# transponder-11_5_2.net
KiCad netlist of a schematic drawn in EAGLE
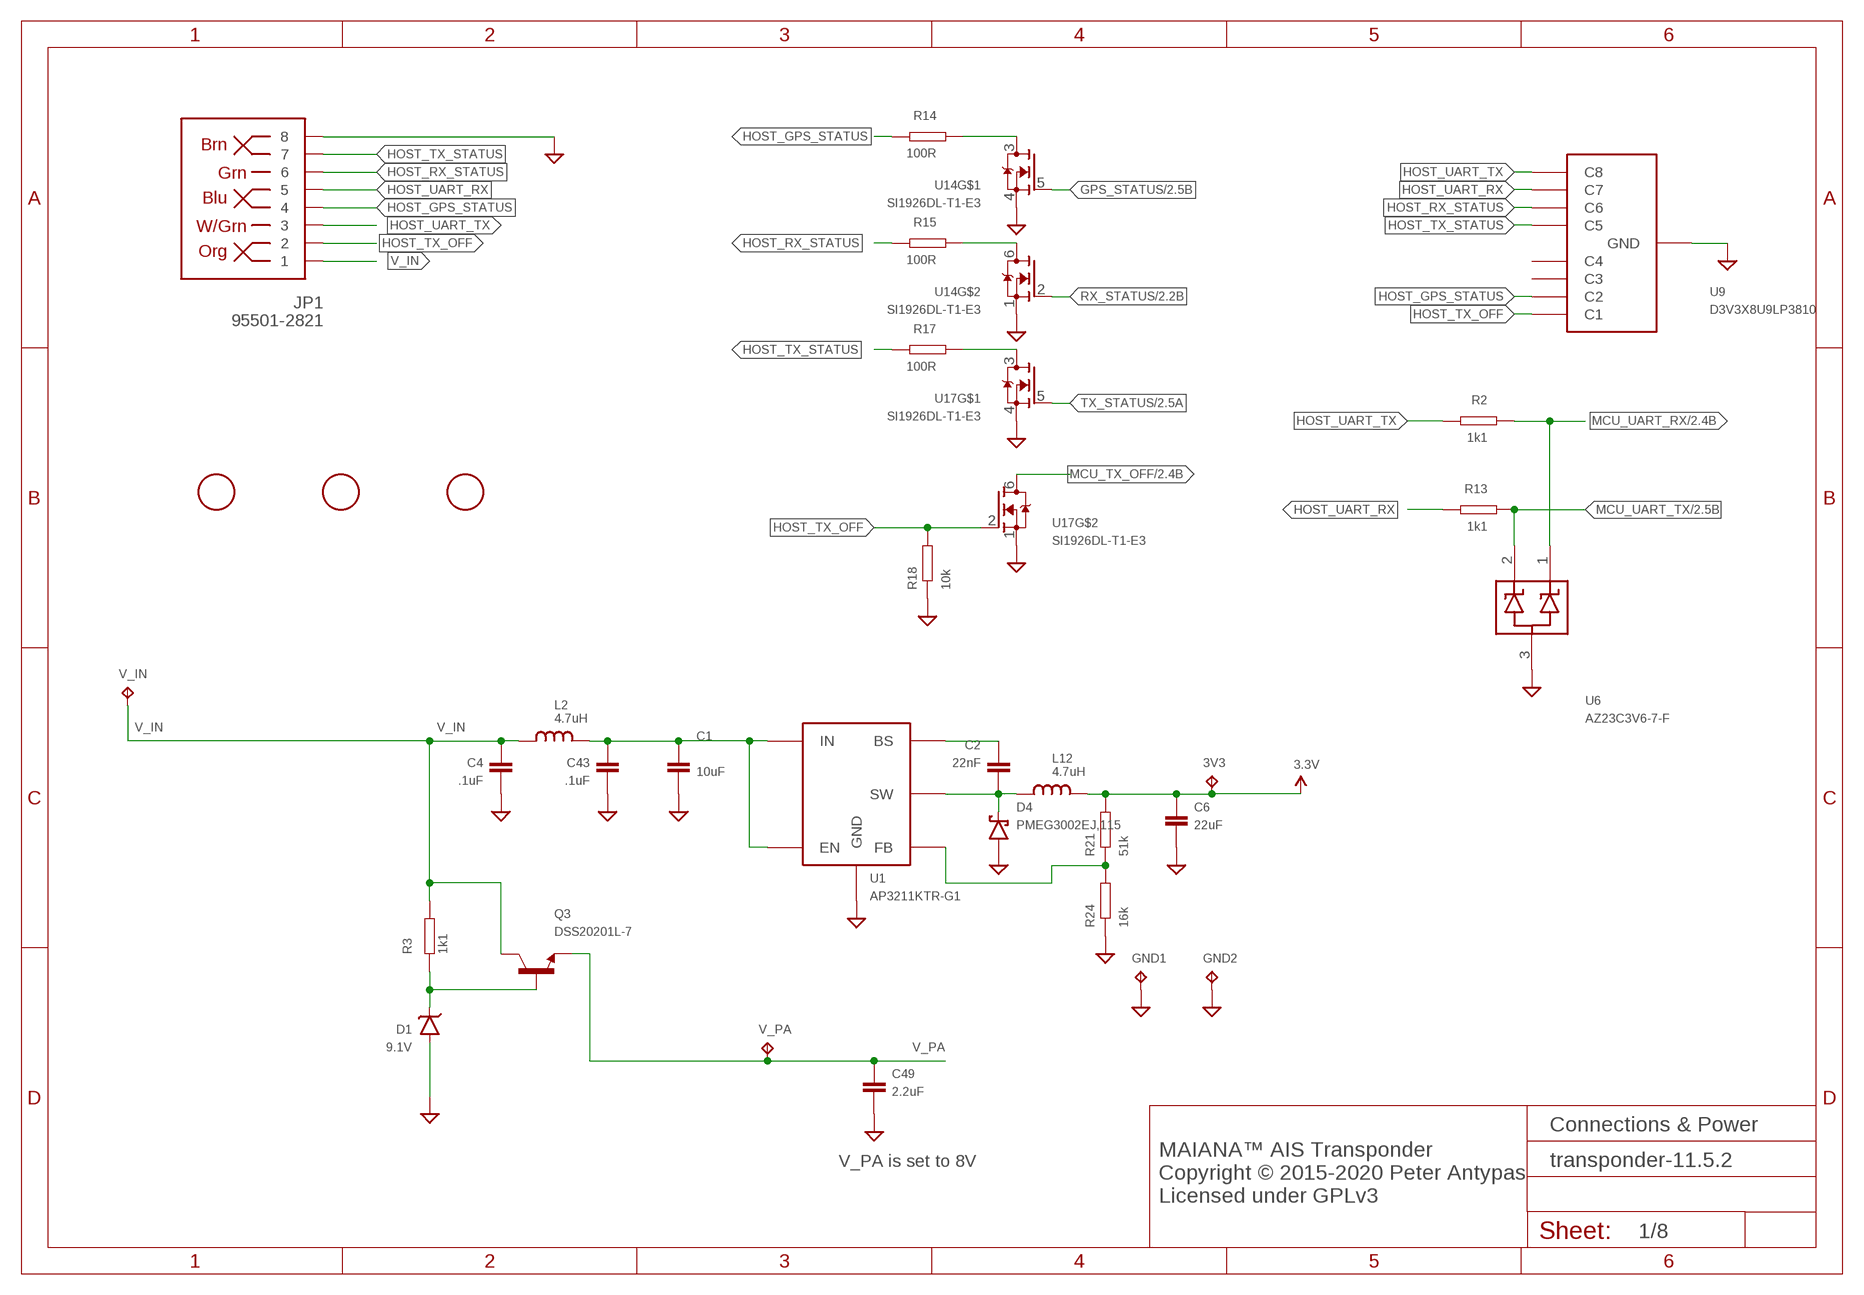
[diagram p0: schematic, sheet 1]
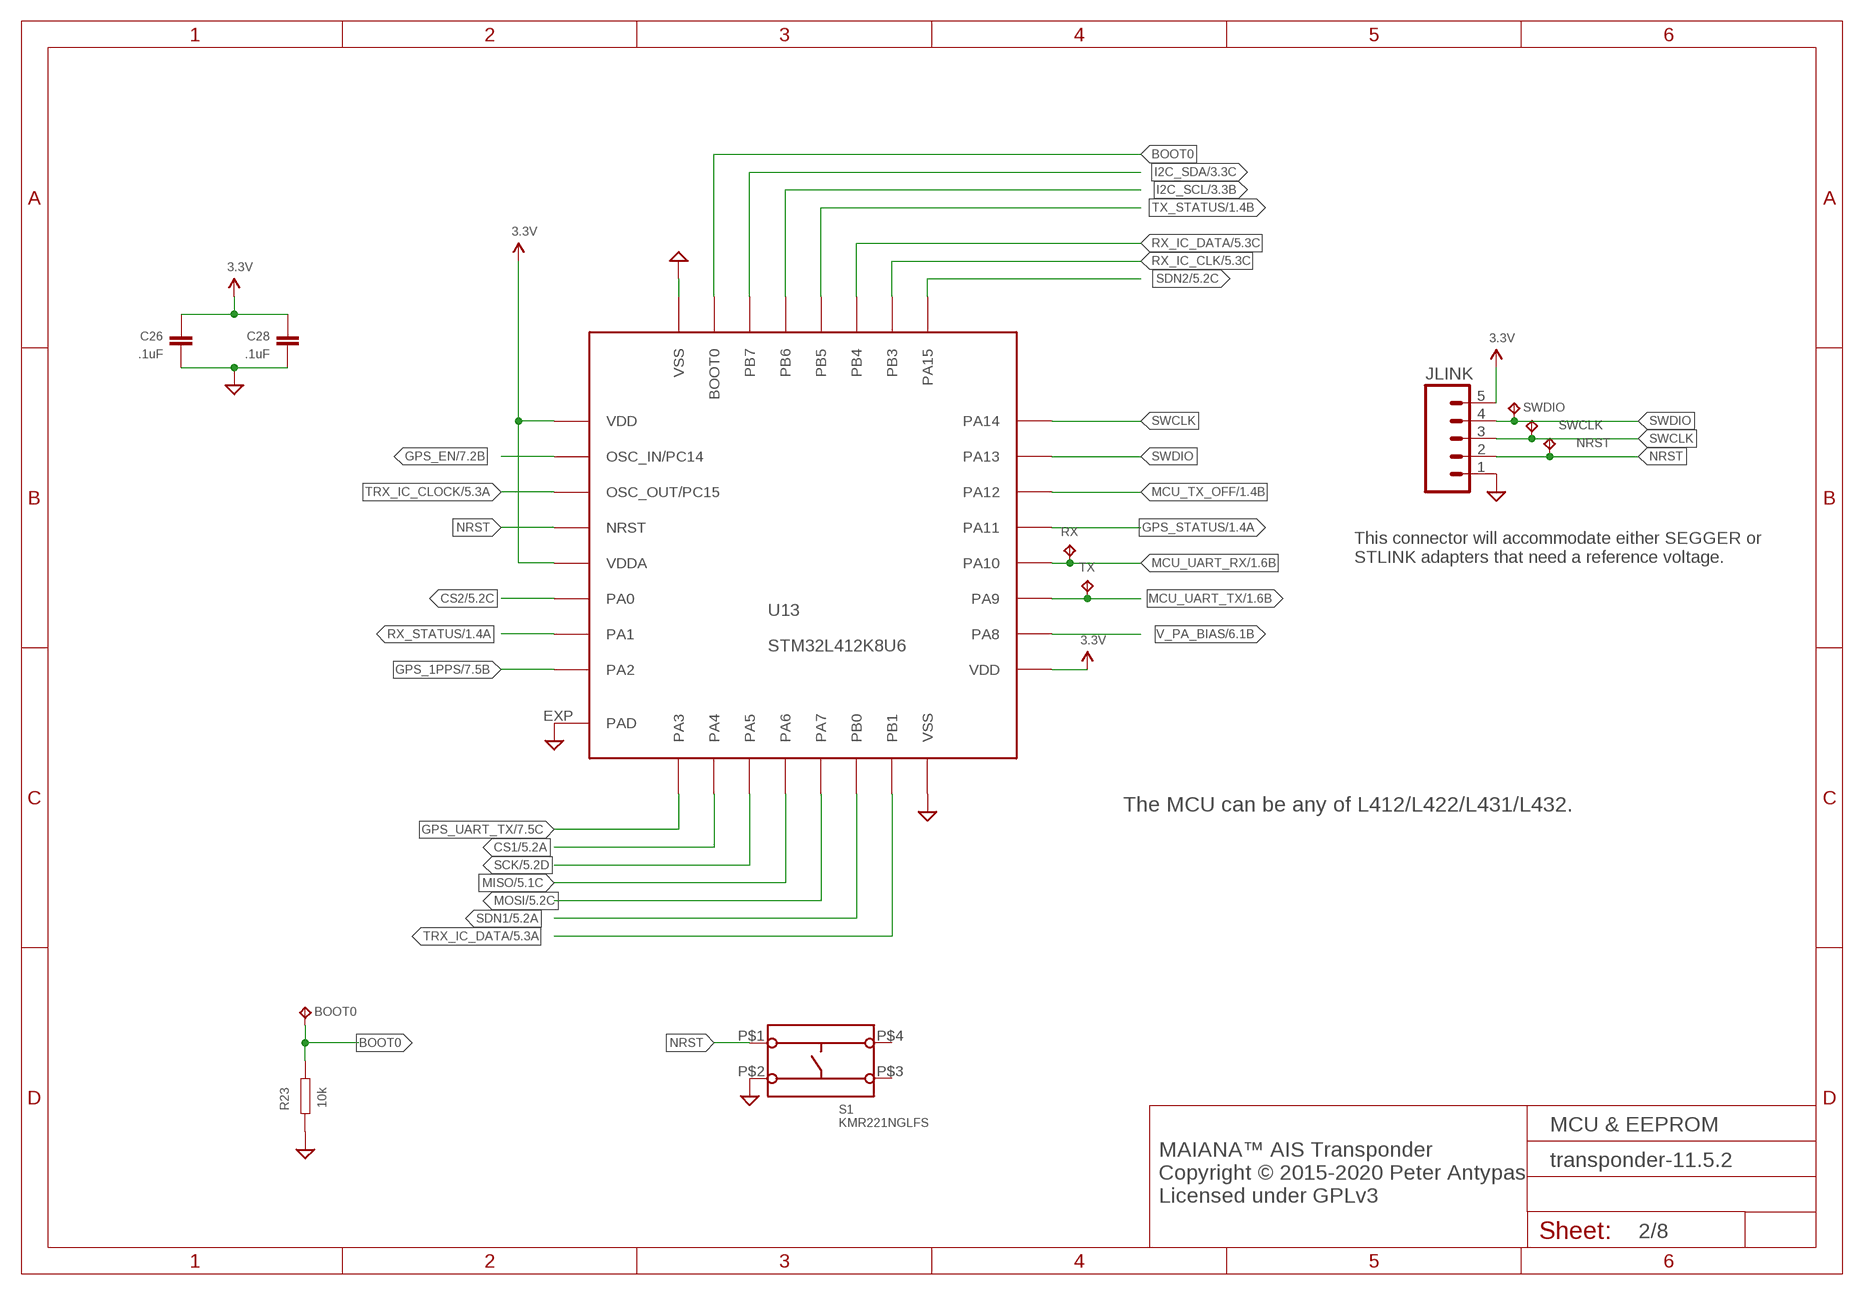
[diagram p1: schematic, sheet 2]
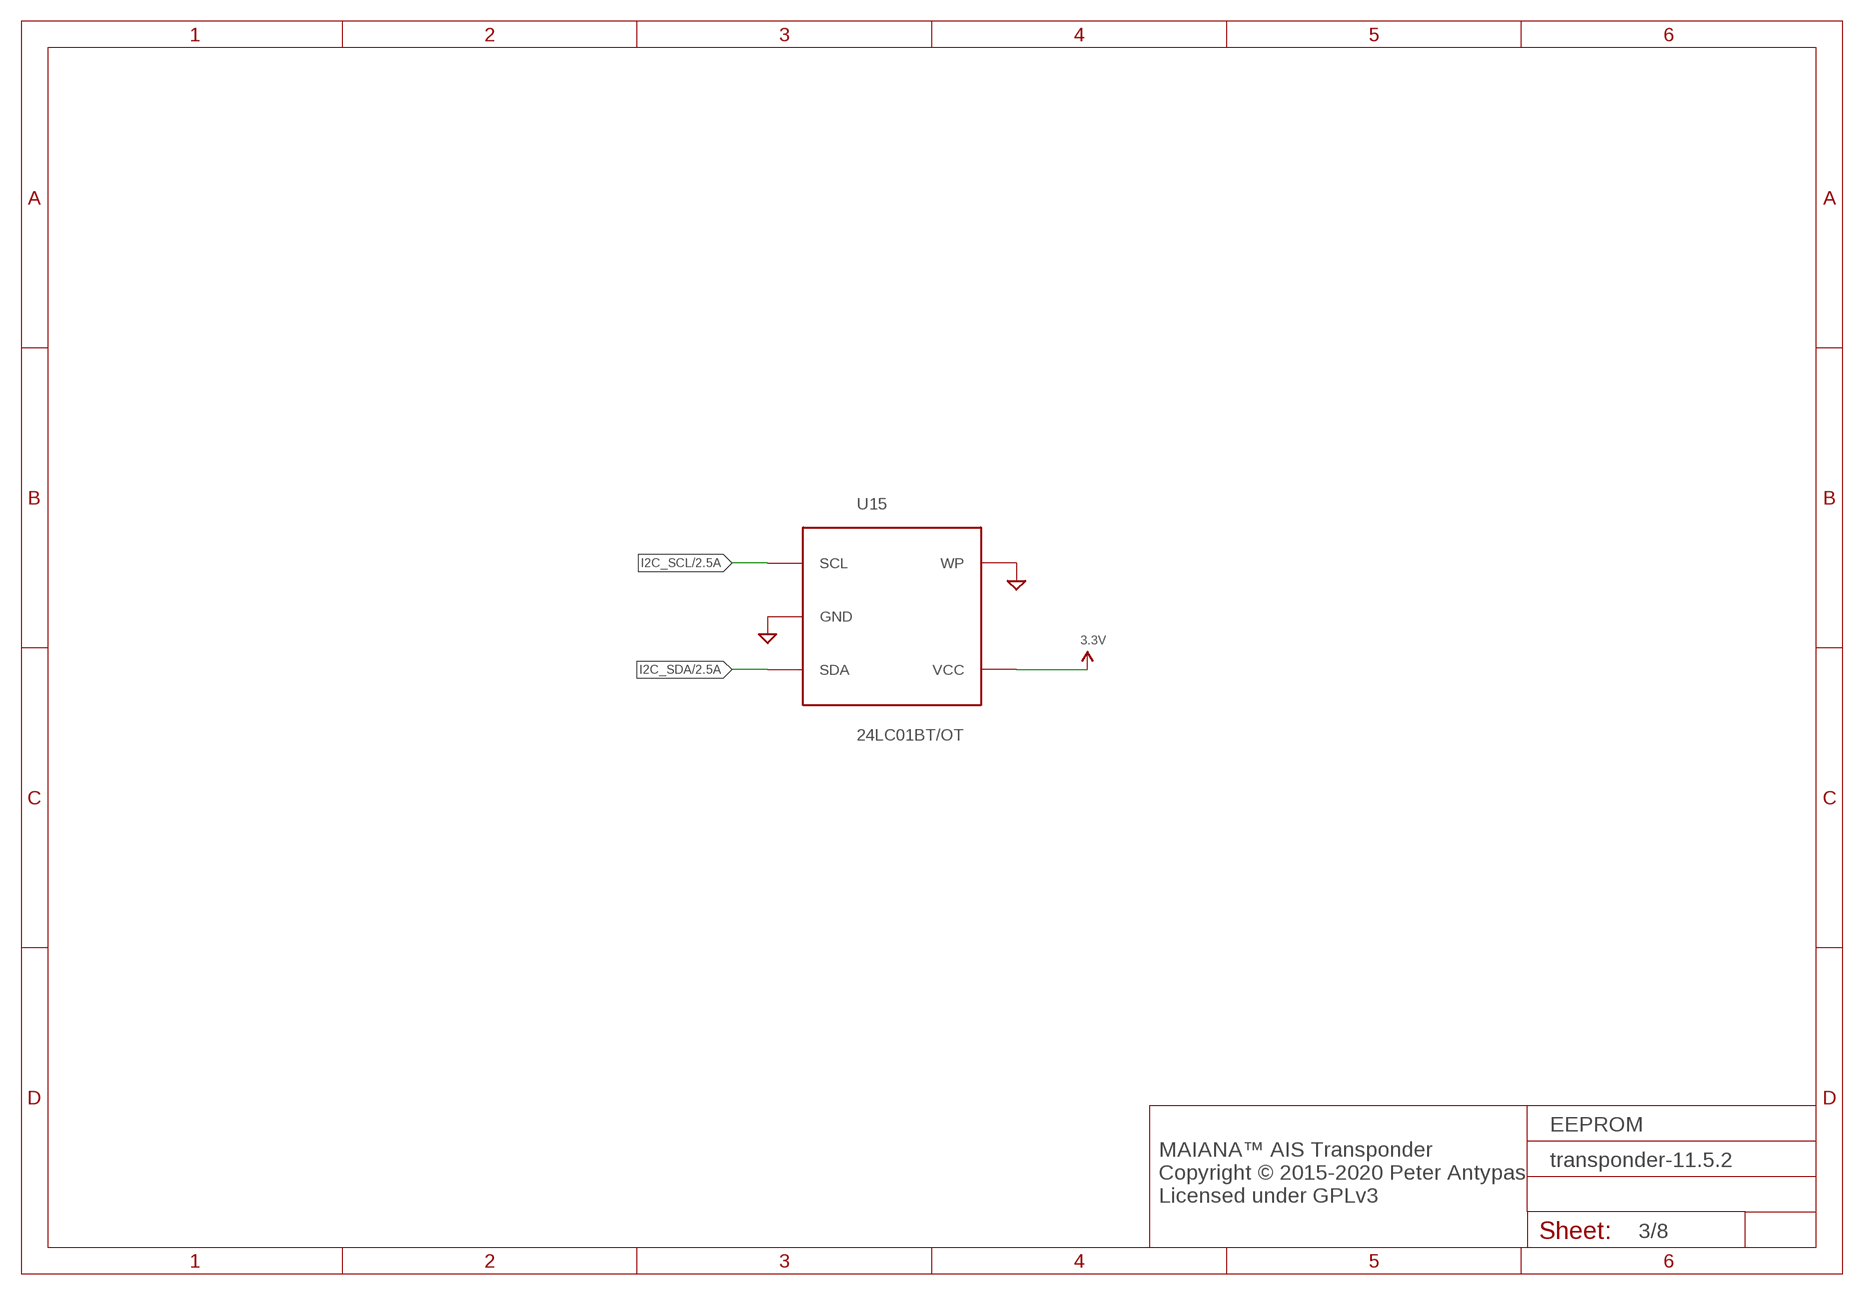
[diagram p2: schematic, sheet 3]
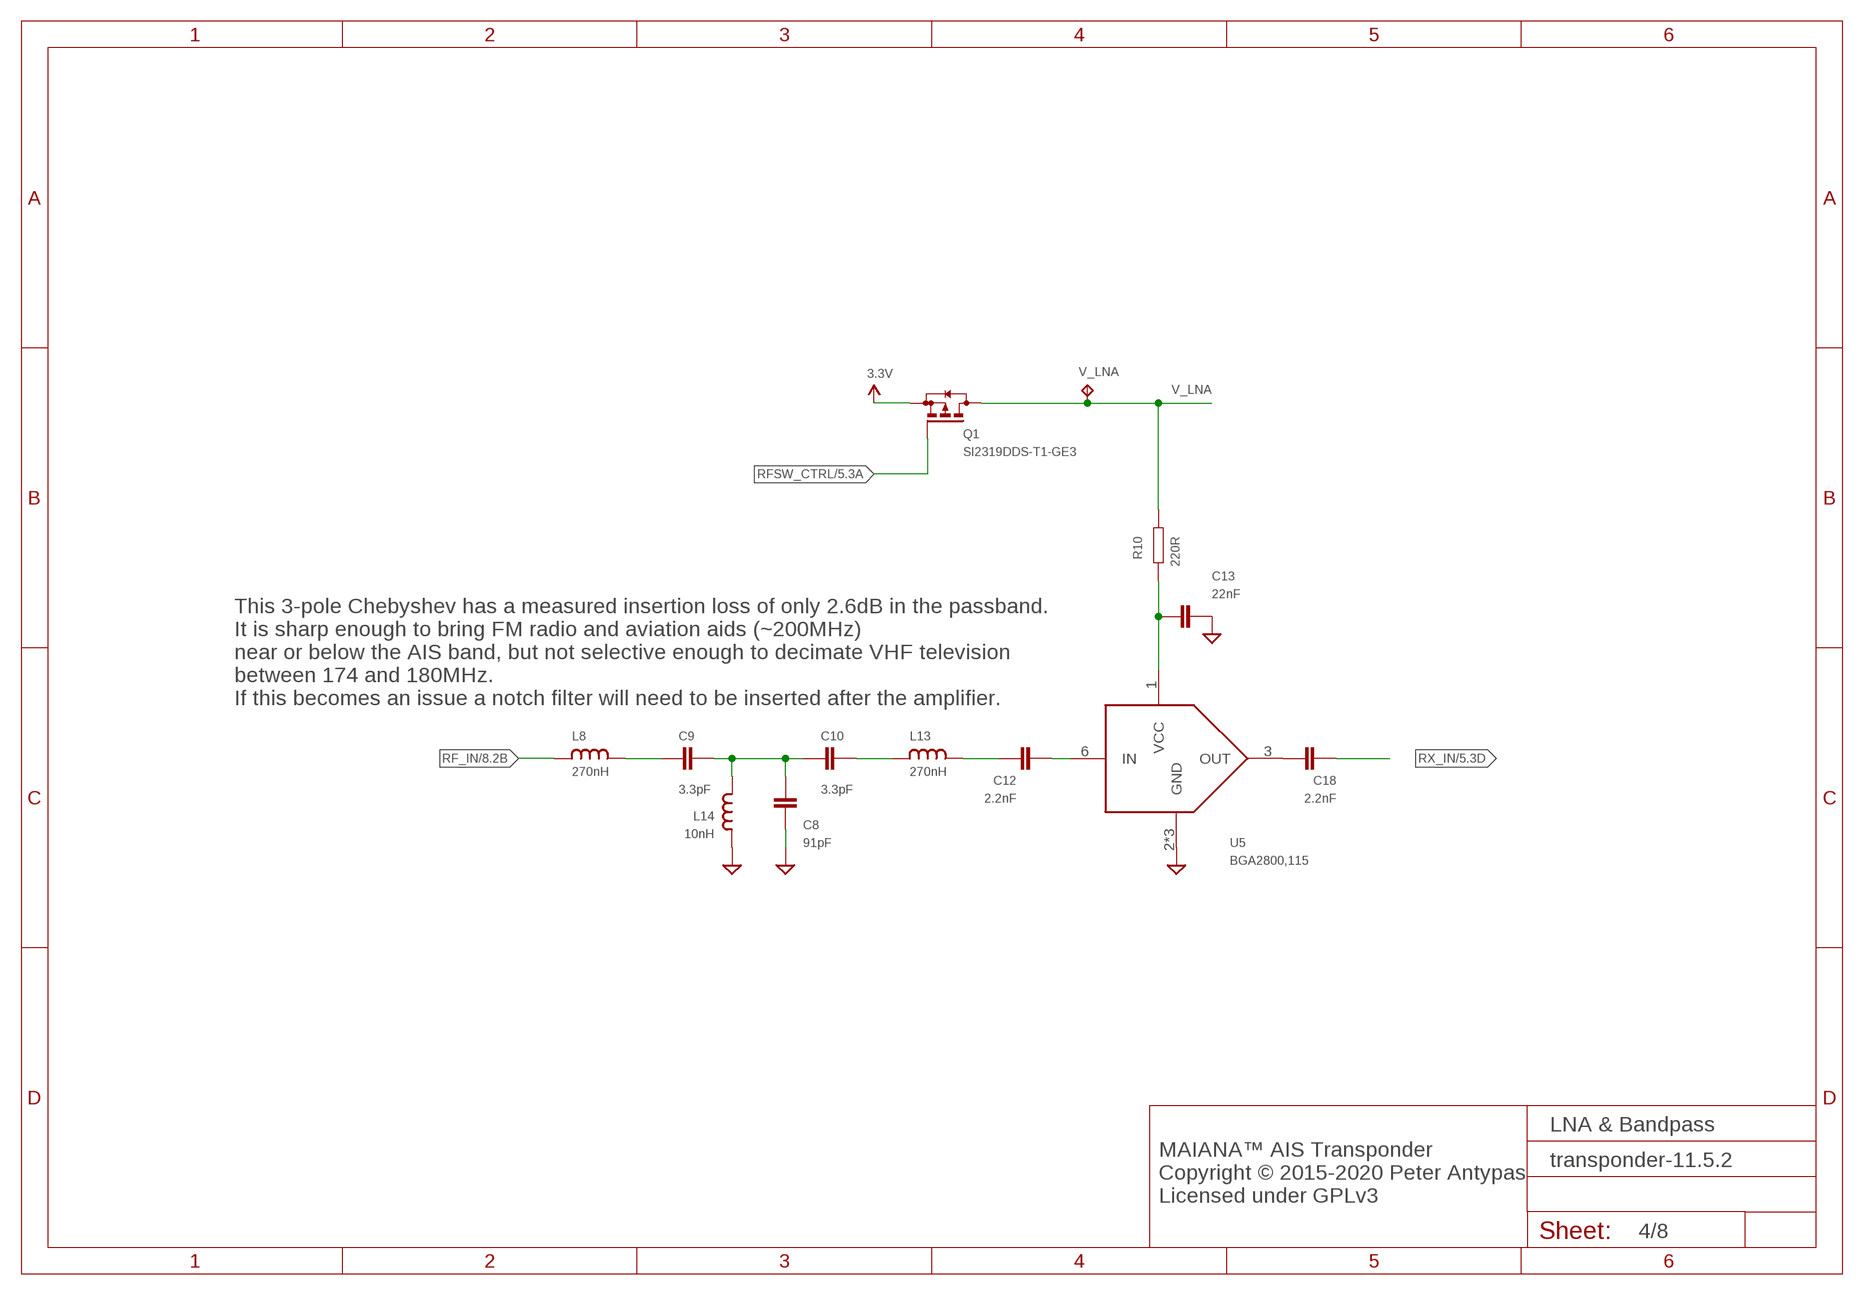
[diagram p3: schematic, sheet 4]
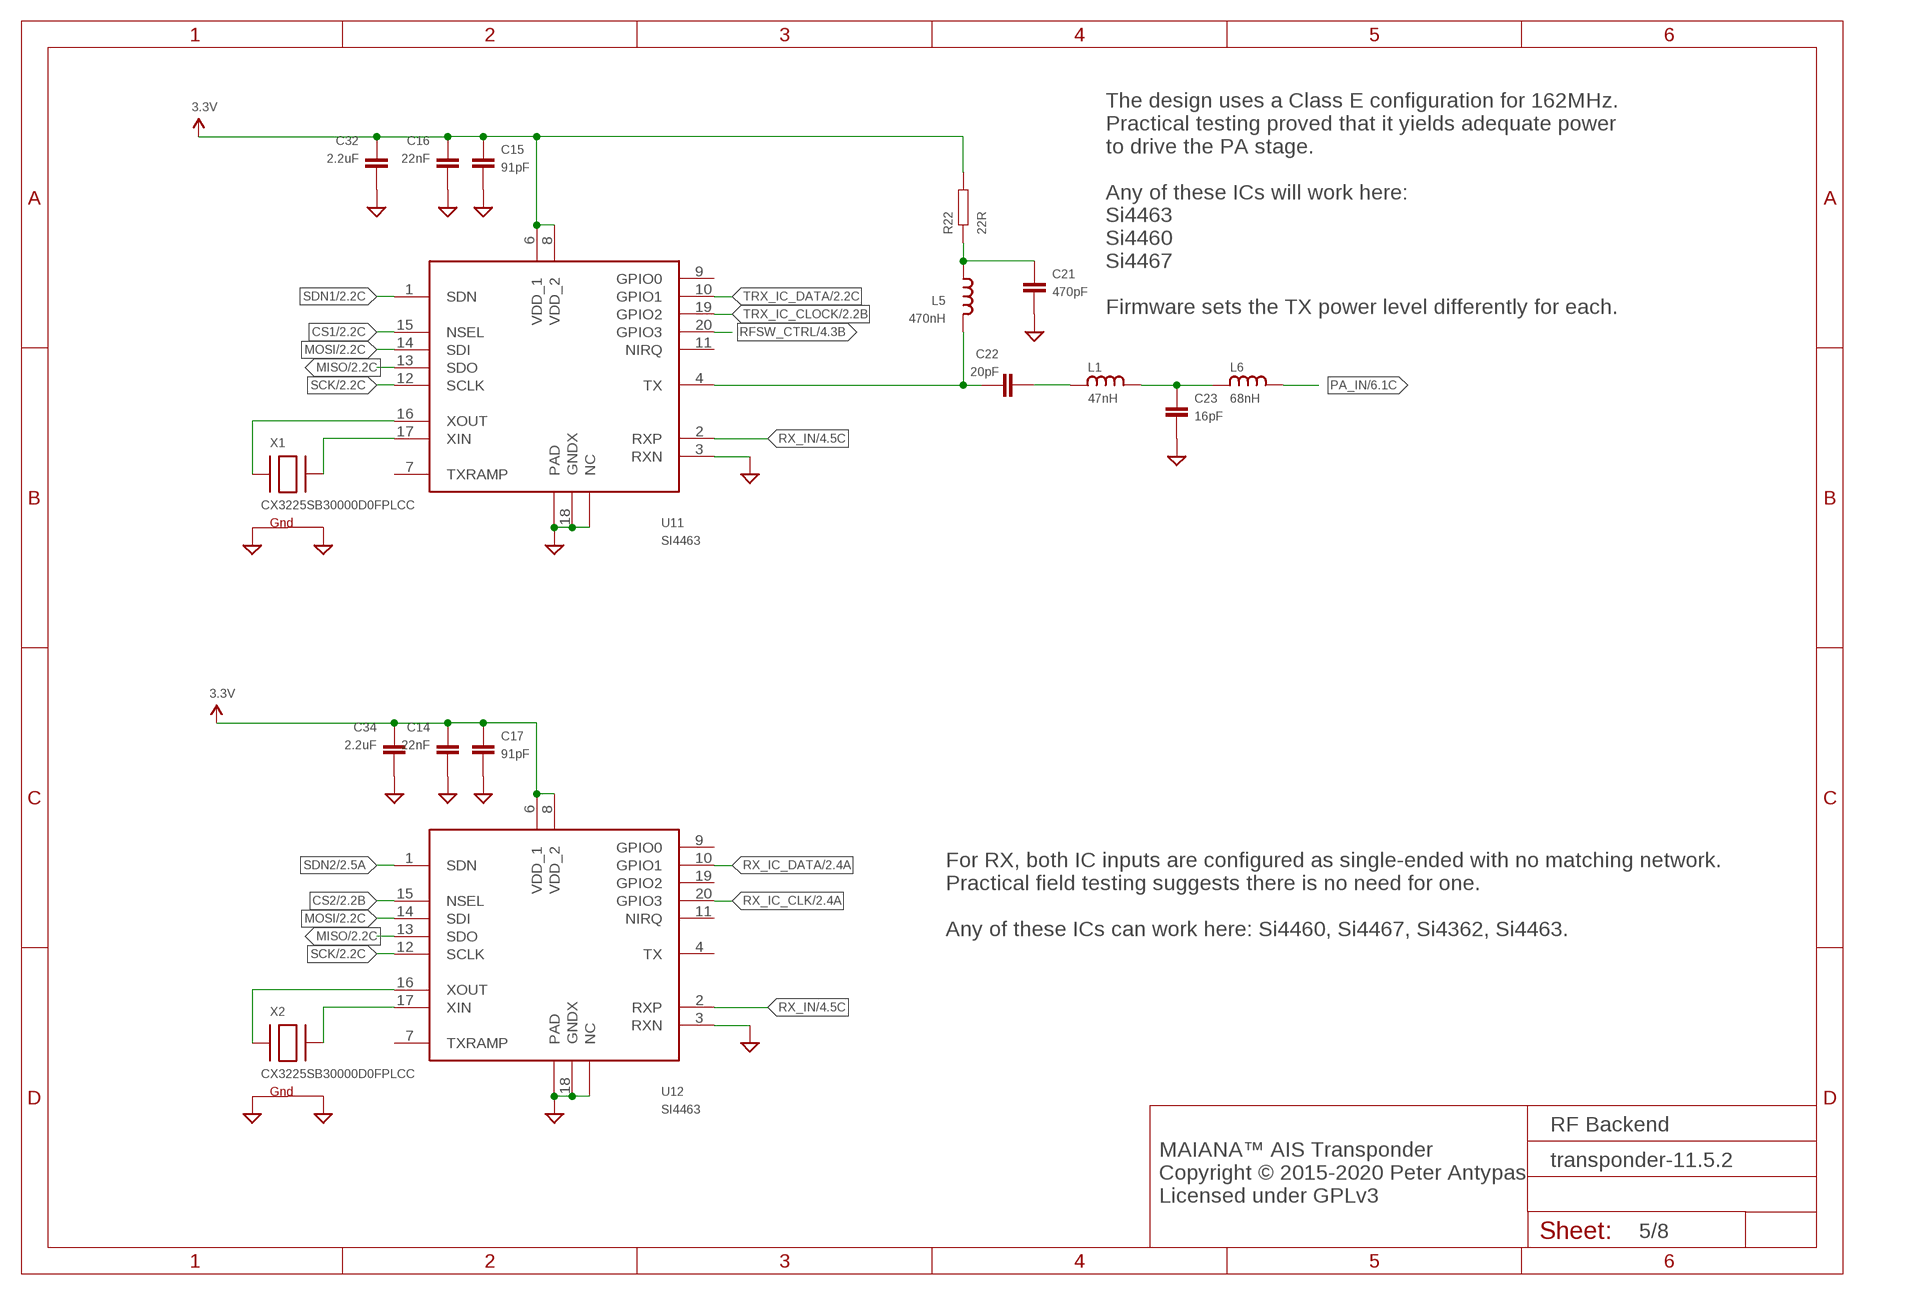
[diagram p4: schematic, sheet 5]
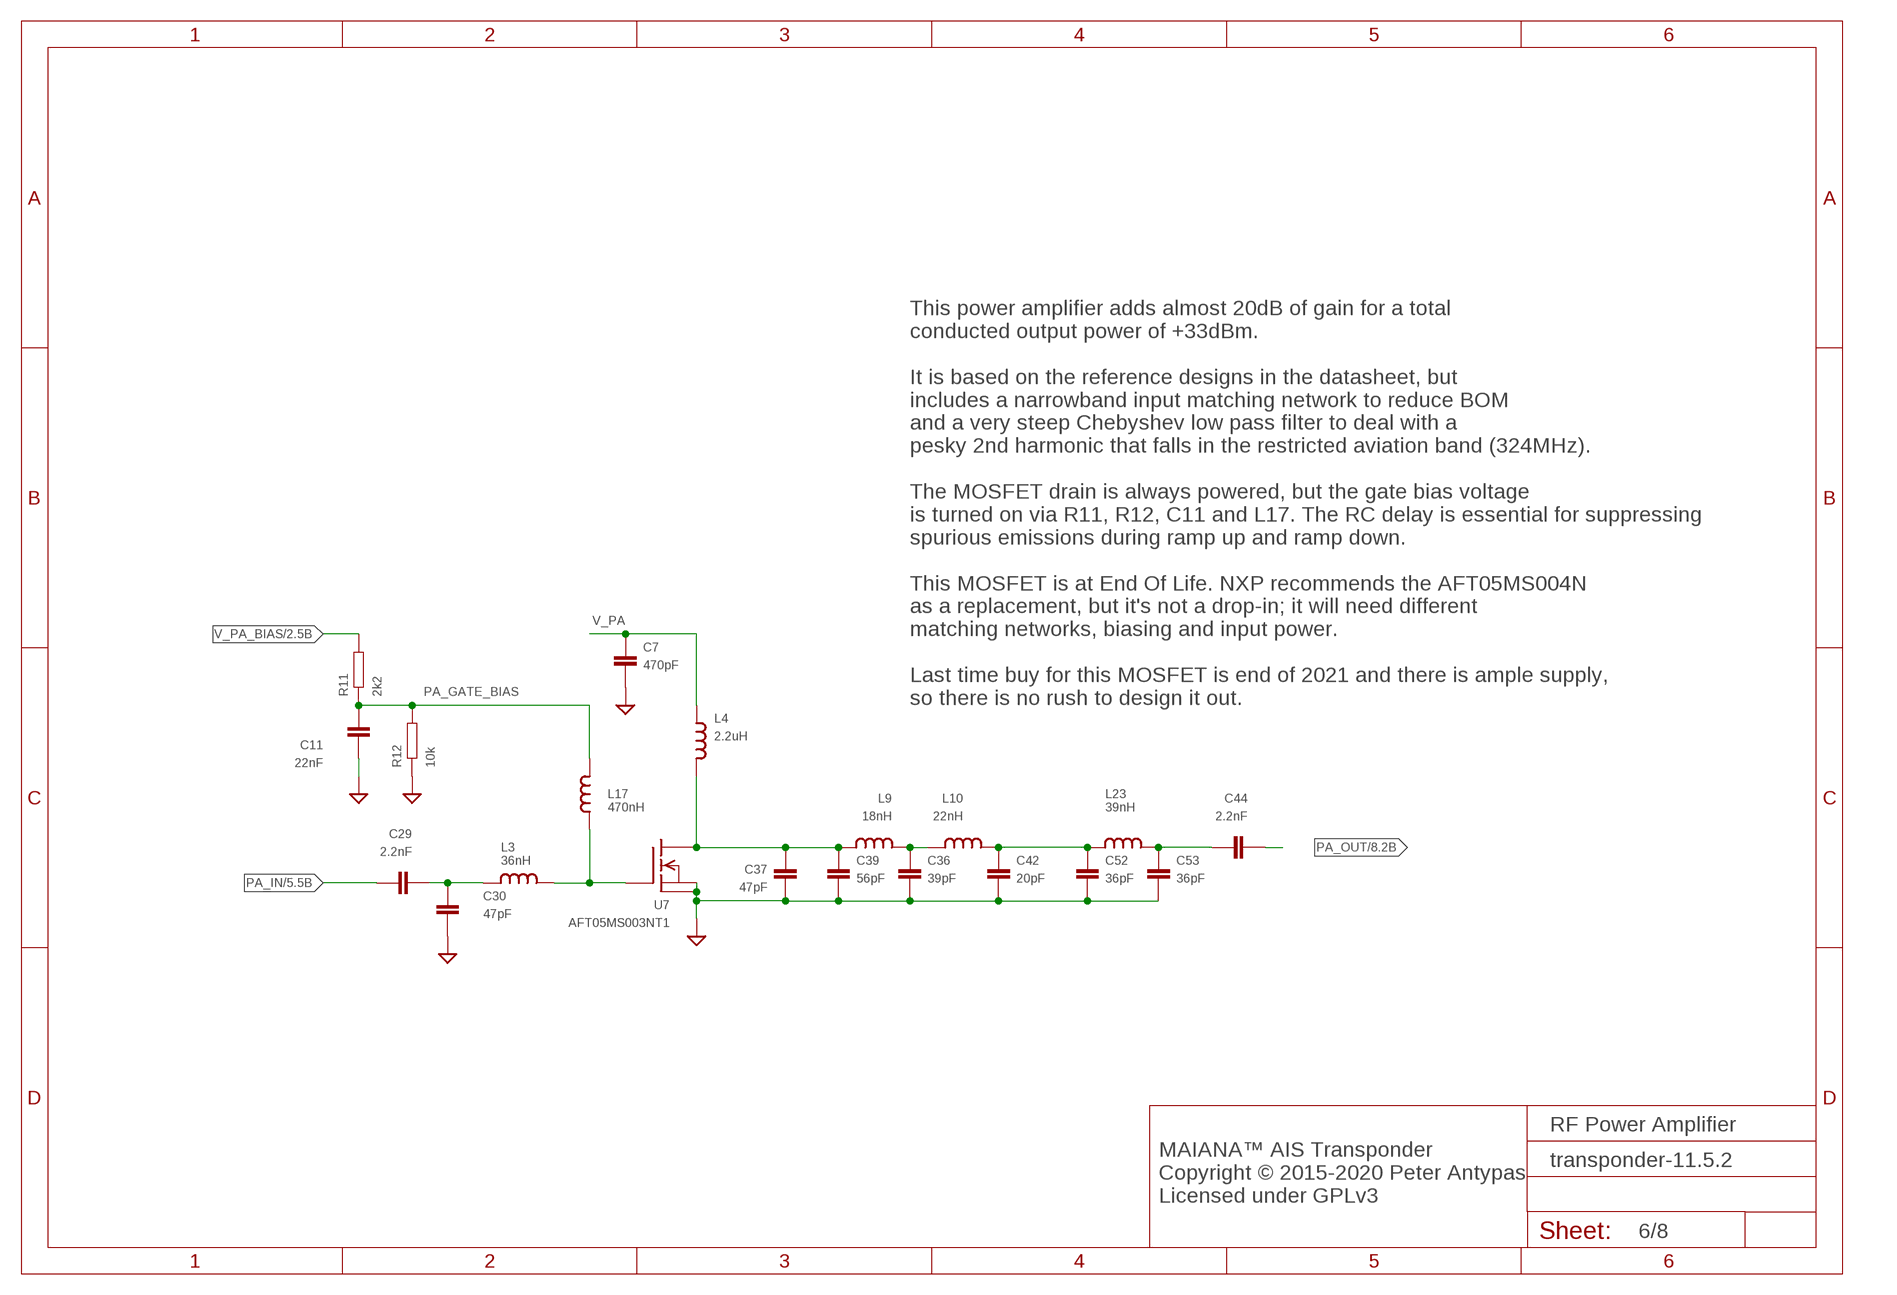
[diagram p5: schematic, sheet 6]
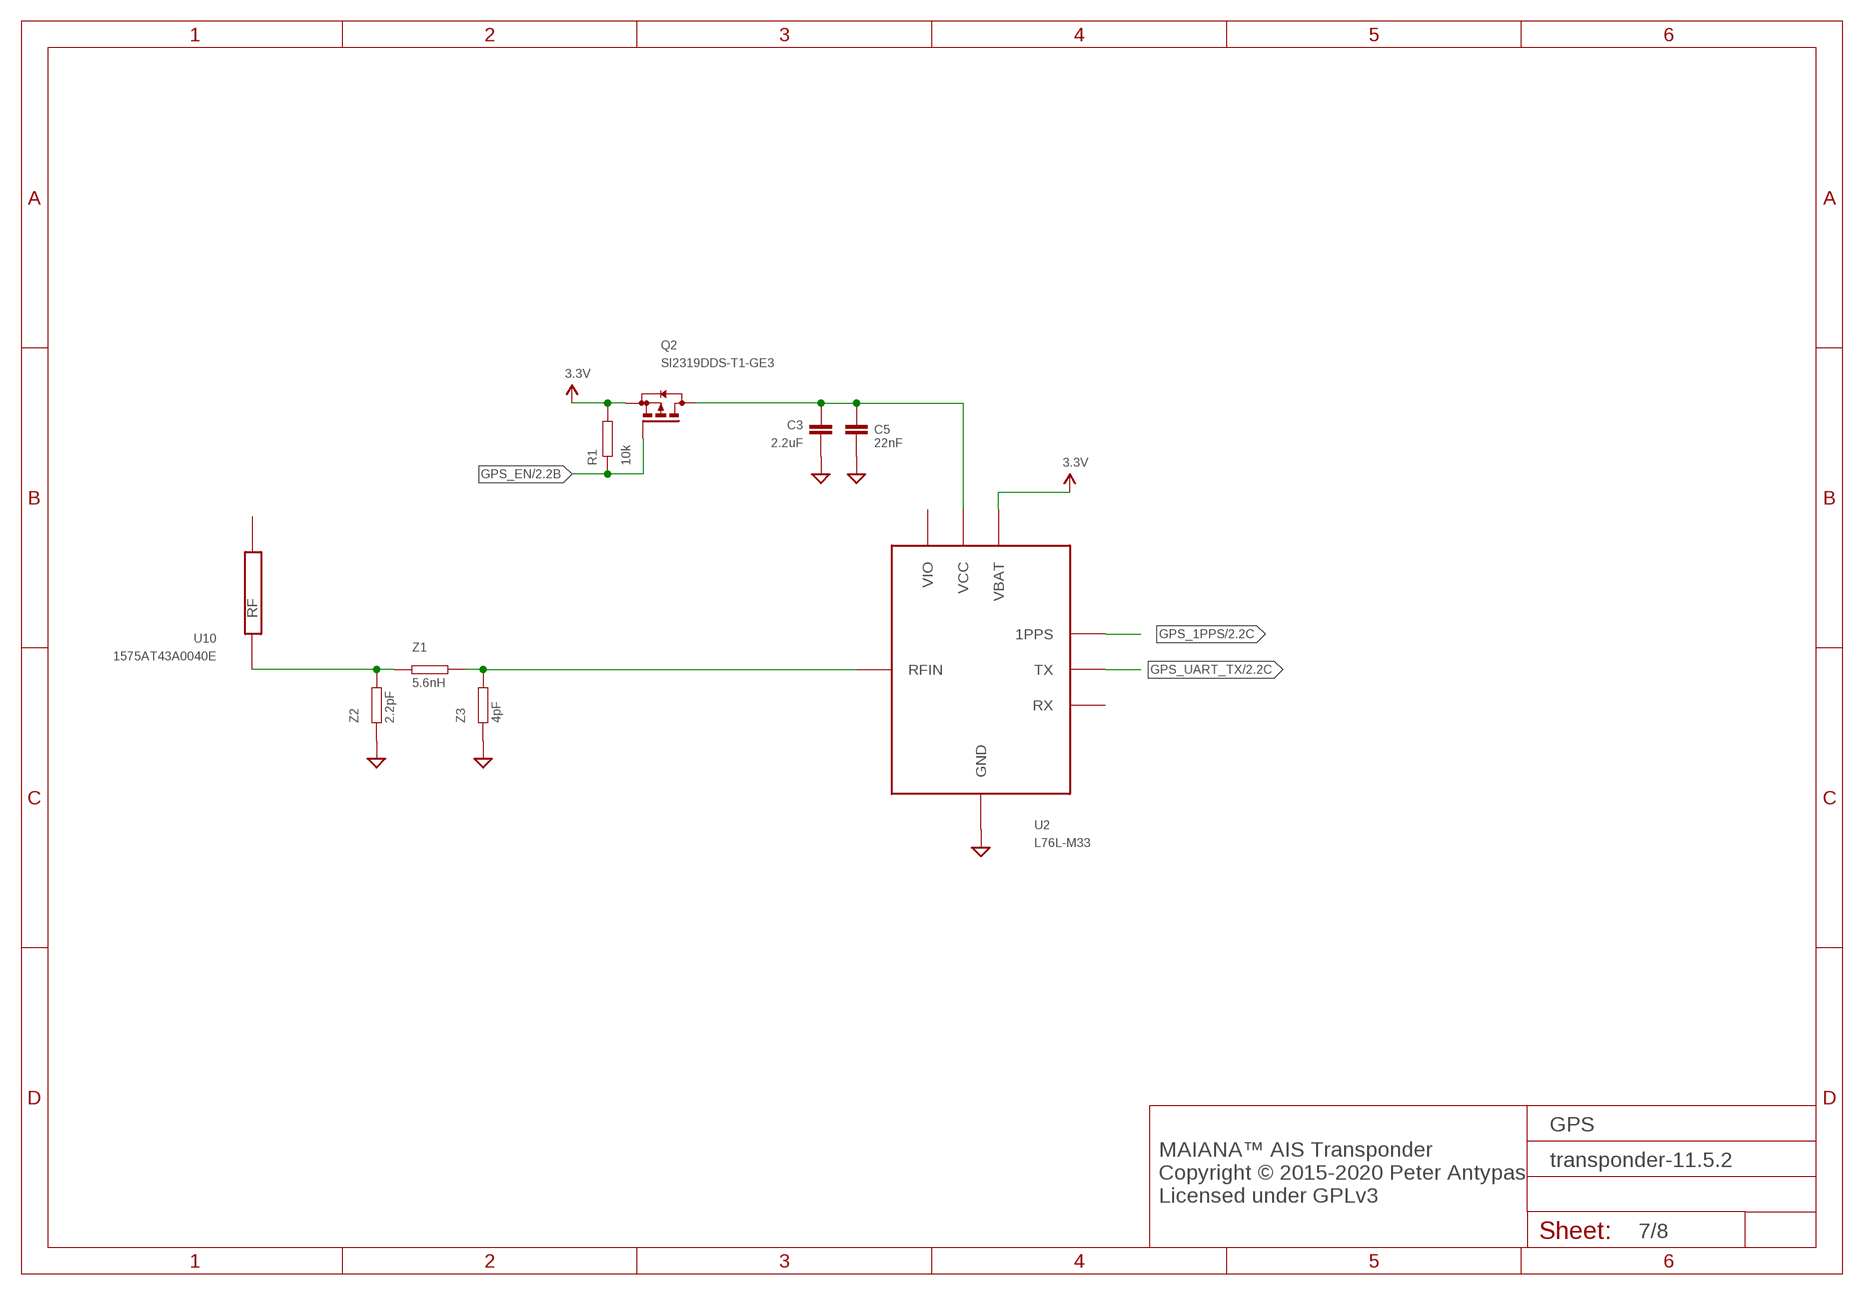
[diagram p6: schematic, sheet 7]
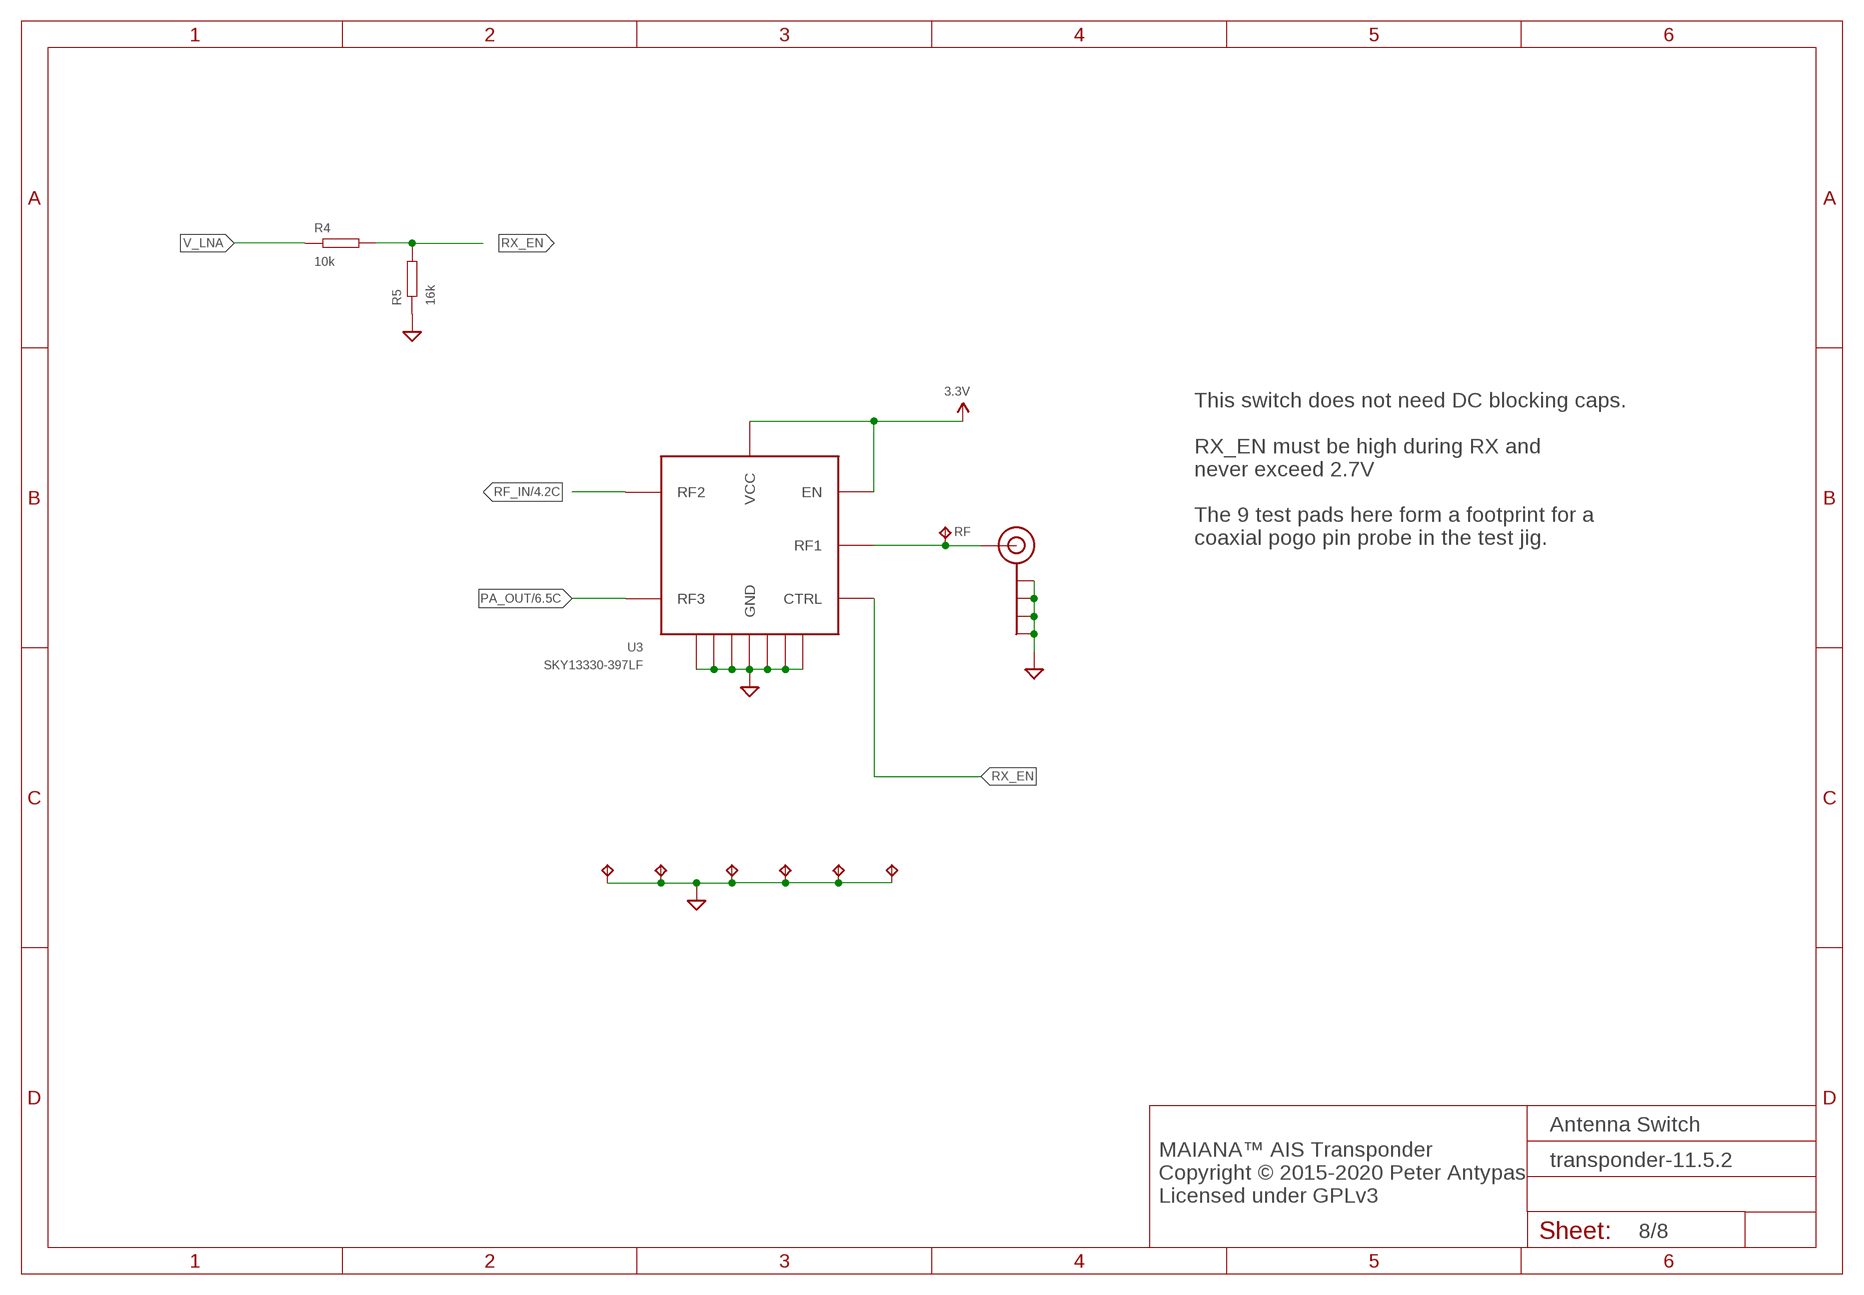
[diagram p7: schematic, sheet 8]

(export (version "E")
  (design (tool "Eeschema 10.0.6"))
  (components
    (comp (ref "C7")
      (value "470pF")
      (footprint "eagle-import:0603")
      (fields (field (name "PARTNO") "GRM1885C1H471JA01D"))
      (libsource (lib "eagle-import") (part "CAPACITOR0603"))
    )
    (comp (ref "C11")
      (value "22nF")
      (footprint "eagle-import:0603")
      (fields (field (name "PARTNO") "GRM188R71E223KA01D"))
      (libsource (lib "eagle-import") (part "CAPACITOR0603"))
    )
    (comp (ref "C29")
      (value "2.2nF")
      (footprint "eagle-import:0603")
      (fields (field (name "PARTNO") "GRM1885C1H222JA01J"))
      (libsource (lib "eagle-import") (part "CAPACITOR0603"))
    )
    (comp (ref "C30")
      (value "47pF")
      (footprint "eagle-import:0603")
      (fields (field (name "PARTNO") "GRM1885C1H470JA01J"))
      (libsource (lib "eagle-import") (part "CAPACITOR0603"))
    )
    (comp (ref "C36")
      (value "39pF")
      (footprint "eagle-import:0603")
      (fields (field (name "PARTNO") "GRM1885C1H390JA01D"))
      (libsource (lib "eagle-import") (part "CAPACITOR0603"))
    )
    (comp (ref "C37")
      (value "47pF")
      (footprint "eagle-import:0603")
      (fields (field (name "PARTNO") "GRM1885C1H470JA01J"))
      (libsource (lib "eagle-import") (part "CAPACITOR0603"))
    )
    (comp (ref "C39")
      (value "56pF")
      (footprint "eagle-import:0603")
      (fields (field (name "PARTNO") "GRM1885C1H560JA01D"))
      (libsource (lib "eagle-import") (part "CAPACITOR0603"))
    )
    (comp (ref "C42")
      (value "20pF")
      (footprint "eagle-import:0603")
      (fields (field (name "PARTNO") "GRM1885C1H200JA01D"))
      (libsource (lib "eagle-import") (part "CAPACITOR0603"))
    )
    (comp (ref "C44")
      (value "2.2nF")
      (footprint "eagle-import:0603")
      (fields (field (name "PARTNO") "GRM1885C1H222JA01J"))
      (libsource (lib "eagle-import") (part "CAPACITOR0603"))
    )
    (comp (ref "C52")
      (value "36pF")
      (footprint "eagle-import:0603")
      (fields (field (name "PARTNO") "06035A360JAT2A"))
      (libsource (lib "eagle-import") (part "CAPACITOR0603"))
    )
    (comp (ref "C53")
      (value "36pF")
      (footprint "eagle-import:0603")
      (fields (field (name "PARTNO") "06035A360JAT2A"))
      (libsource (lib "eagle-import") (part "CAPACITOR0603"))
    )
    (comp (ref "L3")
      (value "36nH")
      (footprint "eagle-import:0603")
      (fields (field (name "PARTNO") "LQW18AN36NG00D"))
      (libsource (lib "eagle-import") (part "INDUCTOR0603"))
    )
    (comp (ref "L4")
      (value "2.2uH")
      (footprint "eagle-import:0805")
      (fields (field (name "PARTNO") "BRC2012T2R2MD"))
      (libsource (lib "eagle-import") (part "INDUCTOR0805"))
    )
    (comp (ref "L9")
      (value "18nH")
      (footprint "eagle-import:0603")
      (fields (field (name "PARTNO") "LQW18AN18NG00D"))
      (libsource (lib "eagle-import") (part "INDUCTOR0603"))
    )
    (comp (ref "L10")
      (value "22nH")
      (footprint "eagle-import:0603")
      (fields (field (name "PARTNO") "LQW18AN22NJ00D"))
      (libsource (lib "eagle-import") (part "INDUCTOR0603"))
    )
    (comp (ref "L17")
      (value "470nH")
      (footprint "eagle-import:0603")
      (fields (field (name "PARTNO") "HK1608R47J-T"))
      (libsource (lib "eagle-import") (part "INDUCTOR0603"))
    )
    (comp (ref "L23")
      (value "39nH")
      (footprint "eagle-import:0603")
      (fields (field (name "PARTNO") "LQW18AN39NG00D"))
      (libsource (lib "eagle-import") (part "INDUCTOR0603"))
    )
    (comp (ref "R11")
      (value "2k2")
      (footprint "eagle-import:0603")
      (fields (field (name "PARTNO") "RC0603FR-072K2L"))
      (libsource (lib "eagle-import") (part "RESISTOR0603"))
    )
    (comp (ref "R12")
      (value "10k")
      (footprint "eagle-import:0603")
      (fields (field (name "PARTNO") "RC0603JR-0710KL"))
      (libsource (lib "eagle-import") (part "RESISTOR0603"))
    )
    (comp (ref "U7")
      (value "AFT05MS003NT1")
      (footprint "eagle-import:SOT-89")
      (libsource (lib "eagle-import") (part "AFT0SMS003N"))
    )
    (comp (ref "J$1")
      (value "SMA_EDGE")
      (footprint "eagle-import:SMA-EDGE")
      (libsource (lib "eagle-import") (part "SMA_EDGE"))
    )
    (comp (ref "R4")
      (value "10k")
      (footprint "eagle-import:0603")
      (fields (field (name "PARTNO") "RC0603JR-0710KL"))
      (libsource (lib "eagle-import") (part "RESISTOR0603"))
    )
    (comp (ref "R5")
      (value "16k")
      (footprint "eagle-import:0603")
      (fields (field (name "PARTNO") "RC0603FR-1016KL"))
      (libsource (lib "eagle-import") (part "RESISTOR0603"))
    )
    (comp (ref "RF")
      (value "TPTP10R")
      (footprint "eagle-import:TP10R")
      (libsource (lib "eagle-import") (part "TPTP10R"))
    )
    (comp (ref "SWDIO1")
      (value "TPTP12R")
      (footprint "eagle-import:TP12R")
      (libsource (lib "eagle-import") (part "TPTP12R"))
    )
    (comp (ref "SWDIO2")
      (value "TPTP12R")
      (footprint "eagle-import:TP12R")
      (libsource (lib "eagle-import") (part "TPTP12R"))
    )
    (comp (ref "SWDIO3")
      (value "TPTP12R")
      (footprint "eagle-import:TP12R")
      (libsource (lib "eagle-import") (part "TPTP12R"))
    )
    (comp (ref "SWDIO4")
      (value "TPTP12R")
      (footprint "eagle-import:TP12R")
      (libsource (lib "eagle-import") (part "TPTP12R"))
    )
    (comp (ref "SWDIO5")
      (value "TPTP12R")
      (footprint "eagle-import:TP12R")
      (libsource (lib "eagle-import") (part "TPTP12R"))
    )
    (comp (ref "SWDIO6")
      (value "TPTP12R")
      (footprint "eagle-import:TP12R")
      (libsource (lib "eagle-import") (part "TPTP12R"))
    )
    (comp (ref "U3")
      (value "SKY13330-397LF")
      (footprint "eagle-import:QFN12")
      (libsource (lib "eagle-import") (part "SKYWORKS-13330397LF"))
    )
    (comp (ref "3V3")
      (value "TPTP12R")
      (footprint "eagle-import:TP12R")
      (libsource (lib "eagle-import") (part "TPTP12R"))
    )
    (comp (ref "C1")
      (value "10uF")
      (footprint "eagle-import:0805")
      (fields (field (name "PARTNO") "EMK212ABJ106KG-T"))
      (libsource (lib "eagle-import") (part "CAPACITOR0805"))
    )
    (comp (ref "C2")
      (value "22nF")
      (footprint "eagle-import:0603")
      (fields (field (name "PARTNO") "GRM188R71E223KA01D"))
      (libsource (lib "eagle-import") (part "CAPACITOR0603"))
    )
    (comp (ref "C4")
      (value ".1uF")
      (footprint "eagle-import:0603")
      (fields (field (name "PARTNO") "EMK107B7104KAHT"))
      (libsource (lib "eagle-import") (part "CAPACITOR0603"))
    )
    (comp (ref "C6")
      (value "22uF")
      (footprint "eagle-import:0805")
      (fields (field (name "PARTNO") "JMK212BBJ226MG8T "))
      (libsource (lib "eagle-import") (part "CAPACITOR0805"))
    )
    (comp (ref "C43")
      (value ".1uF")
      (footprint "eagle-import:0603")
      (fields (field (name "PARTNO") "EMK107B7104KAHT"))
      (libsource (lib "eagle-import") (part "CAPACITOR0603"))
    )
    (comp (ref "C49")
      (value "2.2uF")
      (footprint "eagle-import:0603")
      (fields (field (name "PARTNO") "EMK107BJ225KA-T"))
      (libsource (lib "eagle-import") (part "CAPACITOR0603"))
    )
    (comp (ref "D1")
      (value "9.1V")
      (footprint "eagle-import:SOD323")
      (fields (field (name "PARTNO") "BZX384-B9V1"))
      (libsource (lib "eagle-import") (part "DIODE-ZENERSOD323"))
    )
    (comp (ref "D4")
      (value "PMEG3002EJ,115")
      (footprint "eagle-import:SOD323")
      (fields (field (name "PARTNO") "NSR0240HT1G"))
      (libsource (lib "eagle-import") (part "DIODE-SCHOTTKYSOD323"))
    )
    (comp (ref "GND1")
      (value "TPTP12R")
      (footprint "eagle-import:TP12R")
      (libsource (lib "eagle-import") (part "TPTP12R"))
    )
    (comp (ref "GND2")
      (value "TPTP12R")
      (footprint "eagle-import:TP12R")
      (libsource (lib "eagle-import") (part "TPTP12R"))
    )
    (comp (ref "JP1")
      (value "95501-2821")
      (footprint "eagle-import:RJ45-8")
      (libsource (lib "eagle-import") (part "RJ45-8PTH"))
    )
    (comp (ref "L2")
      (value "4.7uH")
      (footprint "eagle-import:0805")
      (fields (field (name "PARTNO") "MLZ2012M4R7WT000"))
      (libsource (lib "eagle-import") (part "INDUCTOR0805"))
    )
    (comp (ref "L12")
      (value "4.7uH")
      (footprint "eagle-import:0805")
      (fields (field (name "PARTNO") "MLZ2012M4R7WT000"))
      (libsource (lib "eagle-import") (part "INDUCTOR0805"))
    )
    (comp (ref "Q3")
      (value "DSS20201L-7")
      (footprint "eagle-import:SOT23-3")
      (libsource (lib "eagle-import") (part "TRANSISTOR_NPNSOT23-3"))
    )
    (comp (ref "R2")
      (value "1k1")
      (footprint "eagle-import:0603")
      (fields (field (name "PARTNO") "RC0603JR-071K1L "))
      (libsource (lib "eagle-import") (part "RESISTOR0603"))
    )
    (comp (ref "R3")
      (value "1k1")
      (footprint "eagle-import:0603")
      (fields (field (name "PARTNO") "RC0603JR-071K1L "))
      (libsource (lib "eagle-import") (part "RESISTOR0603"))
    )
    (comp (ref "R13")
      (value "1k1")
      (footprint "eagle-import:0603")
      (fields (field (name "PARTNO") "RC0603JR-071K1L "))
      (libsource (lib "eagle-import") (part "RESISTOR0603"))
    )
    (comp (ref "R14")
      (value "100R")
      (footprint "eagle-import:0603")
      (fields (field (name "PARTNO") "RC0603JR-07100RL"))
      (libsource (lib "eagle-import") (part "RESISTOR0603"))
    )
    (comp (ref "R15")
      (value "100R")
      (footprint "eagle-import:0603")
      (fields (field (name "PARTNO") "RC0603JR-07100RL"))
      (libsource (lib "eagle-import") (part "RESISTOR0603"))
    )
    (comp (ref "R17")
      (value "100R")
      (footprint "eagle-import:0603")
      (fields (field (name "PARTNO") "RC0603JR-070RL"))
      (libsource (lib "eagle-import") (part "RESISTOR0603"))
    )
    (comp (ref "R18")
      (value "10k")
      (footprint "eagle-import:0603")
      (fields (field (name "PARTNO") "RC0603JR-0710KL"))
      (libsource (lib "eagle-import") (part "RESISTOR0603"))
    )
    (comp (ref "R21")
      (value "51k")
      (footprint "eagle-import:0603")
      (fields (field (name "PARTNO") "RC0603JR-0751KL"))
      (libsource (lib "eagle-import") (part "RESISTOR0603"))
    )
    (comp (ref "R24")
      (value "16k")
      (footprint "eagle-import:0603")
      (fields (field (name "PARTNO") "RC0603FR-1016KL"))
      (libsource (lib "eagle-import") (part "RESISTOR0603"))
    )
    (comp (ref "U$1")
      (value "FIDUCIAL")
      (footprint "eagle-import:FIDUCIAL_1MM")
      (libsource (lib "eagle-import") (part "FIDUCIAL"))
    )
    (comp (ref "U$2")
      (value "FIDUCIAL")
      (footprint "eagle-import:FIDUCIAL_1MM")
      (libsource (lib "eagle-import") (part "FIDUCIAL"))
    )
    (comp (ref "U$3")
      (value "FIDUCIAL")
      (footprint "eagle-import:FIDUCIAL_1MM")
      (libsource (lib "eagle-import") (part "FIDUCIAL"))
    )
    (comp (ref "U1")
      (value "AP3211KTR-G1")
      (footprint "eagle-import:SOT23-6")
      (libsource (lib "eagle-import") (part "AP3211"))
    )
    (comp (ref "U6")
      (value "AZ23C3V6-7-F")
      (footprint "eagle-import:SOT-23")
      (libsource (lib "eagle-import") (part "AZ23C3V6-7-F"))
    )
    (comp (ref "U9")
      (value "D3V3X8U9LP3810")
      (footprint "eagle-import:U-DFN3810-9(B)")
      (libsource (lib "eagle-import") (part "D3V3X8U9LP3810"))
    )
    (comp (ref "U14")
      (value "SI1926DL-T1-E3")
      (footprint "eagle-import:SOT363")
      (fields (field (name "PARTNO") "SI1926DL-T1-E3 "))
      (libsource (lib "eagle-import") (part "DMN63D8LDW"))
    )
    (comp (ref "U17")
      (value "SI1926DL-T1-E3")
      (footprint "eagle-import:SOT363")
      (fields (field (name "PARTNO") "SI1926DL-T1-E3 "))
      (libsource (lib "eagle-import") (part "DMN63D8LDW"))
    )
    (comp (ref "V_IN")
      (value "TPTP12R")
      (footprint "eagle-import:TP12R")
      (libsource (lib "eagle-import") (part "TPTP12R"))
    )
    (comp (ref "V_PA")
      (value "TPTP12R")
      (footprint "eagle-import:TP12R")
      (libsource (lib "eagle-import") (part "TPTP12R"))
    )
    (comp (ref "C8")
      (value "91pF")
      (footprint "eagle-import:0603")
      (fields (field (name "PARTNO") "GRM1885C2A910JA01D"))
      (libsource (lib "eagle-import") (part "CAPACITOR0603"))
    )
    (comp (ref "C9")
      (value "3.3pF")
      (footprint "eagle-import:0603")
      (fields (field (name "PARTNO") "GRM1885C1H3R3BA01D"))
      (libsource (lib "eagle-import") (part "CAPACITOR0603"))
    )
    (comp (ref "C10")
      (value "3.3pF")
      (footprint "eagle-import:0603")
      (fields (field (name "PARTNO") "GRM1885C1H3R3BA01D"))
      (libsource (lib "eagle-import") (part "CAPACITOR0603"))
    )
    (comp (ref "C12")
      (value "2.2nF")
      (footprint "eagle-import:0603")
      (fields (field (name "PARTNO") "GRM1885C1H222JA01J"))
      (libsource (lib "eagle-import") (part "CAPACITOR0603"))
    )
    (comp (ref "C13")
      (value "22nF")
      (footprint "eagle-import:0603")
      (fields (field (name "PARTNO") "GRM188R71E223KA01D"))
      (libsource (lib "eagle-import") (part "CAPACITOR0603"))
    )
    (comp (ref "C18")
      (value "2.2nF")
      (footprint "eagle-import:0603")
      (fields (field (name "PARTNO") "GRM1885C1H222JA01J"))
      (libsource (lib "eagle-import") (part "CAPACITOR0603"))
    )
    (comp (ref "L8")
      (value "270nH")
      (footprint "eagle-import:0603")
      (fields (field (name "PARTNO") "LQW18ANR27J00D"))
      (libsource (lib "eagle-import") (part "INDUCTOR0603"))
    )
    (comp (ref "L13")
      (value "270nH")
      (footprint "eagle-import:0603")
      (fields (field (name "PARTNO") "LQW18ANR27J00D"))
      (libsource (lib "eagle-import") (part "INDUCTOR0603"))
    )
    (comp (ref "L14")
      (value "10nH")
      (footprint "eagle-import:0603")
      (fields (field (name "PARTNO") "LQW18AN10NG00D"))
      (libsource (lib "eagle-import") (part "INDUCTOR0603"))
    )
    (comp (ref "Q1")
      (value "SI2319DDS-T1-GE3")
      (footprint "eagle-import:SOT23")
      (libsource (lib "eagle-import") (part "BSS84"))
    )
    (comp (ref "R10")
      (value "220R")
      (footprint "eagle-import:0603")
      (fields (field (name "PARTNO") "RC0603JR-07220RL"))
      (libsource (lib "eagle-import") (part "RESISTOR0603"))
    )
    (comp (ref "U5")
      (value "BGA2800,115")
      (footprint "eagle-import:SOT363")
      (libsource (lib "eagle-import") (part "BGA2870"))
    )
    (comp (ref "V_LNA")
      (value "TPTP12R")
      (footprint "eagle-import:TP12R")
      (libsource (lib "eagle-import") (part "TPTP12R"))
    )
    (comp (ref "BOOT0")
      (value "TPTP12R")
      (footprint "eagle-import:TP12R")
      (libsource (lib "eagle-import") (part "TPTP12R"))
    )
    (comp (ref "C26")
      (value ".1uF")
      (footprint "eagle-import:0603")
      (fields (field (name "PARTNO") "EMK107B7104KAHT"))
      (libsource (lib "eagle-import") (part "CAPACITOR0603"))
    )
    (comp (ref "C28")
      (value ".1uF")
      (footprint "eagle-import:0603")
      (fields (field (name "PARTNO") "EMK107B7104KAHT"))
      (libsource (lib "eagle-import") (part "CAPACITOR0603"))
    )
    (comp (ref "JLINK")
      (value "M05PTH")
      (footprint "eagle-import:1X05")
      (libsource (lib "eagle-import") (part "M05PTH"))
    )
    (comp (ref "NRST")
      (value "TPTP12R")
      (footprint "eagle-import:TP12R")
      (libsource (lib "eagle-import") (part "TPTP12R"))
    )
    (comp (ref "R23")
      (value "10k")
      (footprint "eagle-import:0603")
      (fields (field (name "PARTNO") "RC0603JR-0710KL"))
      (libsource (lib "eagle-import") (part "RESISTOR0603"))
    )
    (comp (ref "RX")
      (value "TPTP12R")
      (footprint "eagle-import:TP12R")
      (libsource (lib "eagle-import") (part "TPTP12R"))
    )
    (comp (ref "S1")
      (value "KMR221NGLFS")
      (footprint "eagle-import:KMR221NGLFS")
      (libsource (lib "eagle-import") (part "KMR221NGLFS"))
    )
    (comp (ref "SWCLK")
      (value "TPTP12R")
      (footprint "eagle-import:TP12R")
      (libsource (lib "eagle-import") (part "TPTP12R"))
    )
    (comp (ref "SWDIO")
      (value "TPTP12R")
      (footprint "eagle-import:TP12R")
      (libsource (lib "eagle-import") (part "TPTP12R"))
    )
    (comp (ref "TX")
      (value "TPTP12R")
      (footprint "eagle-import:TP12R")
      (libsource (lib "eagle-import") (part "TPTP12R"))
    )
    (comp (ref "U13")
      (value "STM32L412K8U6")
      (footprint "eagle-import:QFN32")
      (libsource (lib "eagle-import") (part "STM32L432KXXX"))
    )
    (comp (ref "C14")
      (value "22nF")
      (footprint "eagle-import:0603")
      (fields (field (name "PARTNO") "GRM188R71E223KA01D"))
      (libsource (lib "eagle-import") (part "CAPACITOR0603"))
    )
    (comp (ref "C15")
      (value "91pF")
      (footprint "eagle-import:0603")
      (fields (field (name "PARTNO") "GRM1885C2A910JA01D"))
      (libsource (lib "eagle-import") (part "CAPACITOR0603"))
    )
    (comp (ref "C16")
      (value "22nF")
      (footprint "eagle-import:0603")
      (fields (field (name "PARTNO") "GRM188R71E223KA01D"))
      (libsource (lib "eagle-import") (part "CAPACITOR0603"))
    )
    (comp (ref "C17")
      (value "91pF")
      (footprint "eagle-import:0603")
      (fields (field (name "PARTNO") "GRM1885C2A910JA01D"))
      (libsource (lib "eagle-import") (part "CAPACITOR0603"))
    )
    (comp (ref "C21")
      (value "470pF")
      (footprint "eagle-import:0603")
      (fields (field (name "PARTNO") "GRM1885C1H471JA01D"))
      (libsource (lib "eagle-import") (part "CAPACITOR0603"))
    )
    (comp (ref "C22")
      (value "20pF")
      (footprint "eagle-import:0603")
      (fields (field (name "PARTNO") "GRM1885C1H200JA01D"))
      (libsource (lib "eagle-import") (part "CAPACITOR0603"))
    )
    (comp (ref "C23")
      (value "16pF")
      (footprint "eagle-import:0603")
      (fields (field (name "PARTNO") "GCM1885C2A160JA16D"))
      (libsource (lib "eagle-import") (part "CAPACITOR0603"))
    )
    (comp (ref "C32")
      (value "2.2uF")
      (footprint "eagle-import:0603")
      (fields (field (name "PARTNO") "EMK107BJ225KA-T"))
      (libsource (lib "eagle-import") (part "CAPACITOR0603"))
    )
    (comp (ref "C34")
      (value "2.2uF")
      (footprint "eagle-import:0603")
      (fields (field (name "PARTNO") "EMK107BJ225KA-T"))
      (libsource (lib "eagle-import") (part "CAPACITOR0603"))
    )
    (comp (ref "L1")
      (value "47nH")
      (footprint "eagle-import:0603")
      (fields (field (name "PARTNO") "LQW18AN47NG00D"))
      (libsource (lib "eagle-import") (part "INDUCTOR0603"))
    )
    (comp (ref "L5")
      (value "470nH")
      (footprint "eagle-import:0603")
      (fields (field (name "PARTNO") "HK1608R47J-T"))
      (libsource (lib "eagle-import") (part "INDUCTOR0603"))
    )
    (comp (ref "L6")
      (value "68nH")
      (footprint "eagle-import:0603")
      (fields (field (name "PARTNO") "LQW18AN68NG00D "))
      (libsource (lib "eagle-import") (part "INDUCTOR0603"))
    )
    (comp (ref "R22")
      (value "22R")
      (footprint "eagle-import:0603")
      (fields (field (name "PARTNO") "RC0603JR-0722RL"))
      (libsource (lib "eagle-import") (part "RESISTOR0603"))
    )
    (comp (ref "U11")
      (value "SI4463")
      (footprint "eagle-import:QFN20")
      (fields (field (name "PARTNO") "SI4463-C2A-GMR"))
      (libsource (lib "eagle-import") (part "SI4463"))
    )
    (comp (ref "U12")
      (value "SI4463")
      (footprint "eagle-import:QFN20")
      (fields (field (name "PARTNO") "SI4463-C2A-GMR"))
      (libsource (lib "eagle-import") (part "SI4463"))
    )
    (comp (ref "X1")
      (value "CX3225SB30000D0FPLCC")
      (footprint "eagle-import:NX3225")
      (libsource (lib "eagle-import") (part "XTAL-4-3225"))
    )
    (comp (ref "X2")
      (value "CX3225SB30000D0FPLCC")
      (footprint "eagle-import:NX3225")
      (libsource (lib "eagle-import") (part "XTAL-4-3225"))
    )
    (comp (ref "U15")
      (value "24LC01BT/OT")
      (footprint "eagle-import:SOT23-5")
      (fields (field (name "PARTNO") "24LC01BT/OT "))
      (libsource (lib "eagle-import") (part "24LC01B"))
    )
    (comp (ref "C3")
      (value "2.2uF")
      (footprint "eagle-import:0603")
      (fields (field (name "PARTNO") "EMK107BJ225KA-T"))
      (libsource (lib "eagle-import") (part "CAPACITOR0603"))
    )
    (comp (ref "C5")
      (value "22nF")
      (footprint "eagle-import:0603")
      (fields (field (name "PARTNO") "GRM188R71E223KA01D"))
      (libsource (lib "eagle-import") (part "CAPACITOR0603"))
    )
    (comp (ref "Q2")
      (value "SI2319DDS-T1-GE3")
      (footprint "eagle-import:SOT23")
      (libsource (lib "eagle-import") (part "BSS84"))
    )
    (comp (ref "R1")
      (value "10k")
      (footprint "eagle-import:0603")
      (fields (field (name "PARTNO") "RC0603JR-0710KL"))
      (libsource (lib "eagle-import") (part "RESISTOR0603"))
    )
    (comp (ref "U2")
      (value "L76L-M33")
      (footprint "eagle-import:GPS_MODULE")
      (fields (field (name "PARTNO") "L70B-M39"))
      (libsource (lib "eagle-import") (part "L70"))
    )
    (comp (ref "U10")
      (value "1575AT43A0040E")
      (footprint "eagle-import:1575AT43A0040E")
      (libsource (lib "eagle-import") (part "1575AT43A0040E"))
    )
    (comp (ref "Z1")
      (value "5.6nH")
      (footprint "eagle-import:0603")
      (fields (field (name "PARTNO") "‎GRM1885C1H120GA01D‎"))
      (libsource (lib "eagle-import") (part "RESISTOR0603"))
    )
    (comp (ref "Z2")
      (value "2.2pF")
      (footprint "eagle-import:0603")
      (fields (field (name "PARTNO") "0603N2R2B500CT"))
      (libsource (lib "eagle-import") (part "RESISTOR0603"))
    )
    (comp (ref "Z3")
      (value "4pF")
      (footprint "eagle-import:0603")
      (fields (field (name "PARTNO") "‎GRM1885C1H120GA01D‎"))
      (libsource (lib "eagle-import") (part "RESISTOR0603"))
    )
  )
  (nets
    (net (code "1") (name "3.3V") (class "Default")
      (node (ref "3V3") (pin "TP") (pinfunction "TP_TP") (pintype "input"))
      (node (ref "C14") (pin "P$1") (pinfunction "1_P$1") (pintype "passive"))
      (node (ref "C15") (pin "P$1") (pinfunction "1_P$1") (pintype "passive"))
      (node (ref "C16") (pin "P$1") (pinfunction "1_P$1") (pintype "passive"))
      (node (ref "C17") (pin "P$1") (pinfunction "1_P$1") (pintype "passive"))
      (node (ref "C26") (pin "P$1") (pinfunction "1_P$1") (pintype "passive"))
      (node (ref "C28") (pin "P$1") (pinfunction "1_P$1") (pintype "passive"))
      (node (ref "C32") (pin "P$1") (pinfunction "1_P$1") (pintype "passive"))
      (node (ref "C34") (pin "P$1") (pinfunction "1_P$1") (pintype "passive"))
      (node (ref "C6") (pin "P$1") (pinfunction "1_P$1") (pintype "passive"))
      (node (ref "JLINK") (pin "5") (pinfunction "5_5") (pintype "passive"))
      (node (ref "L12") (pin "P$2") (pinfunction "2_P$2") (pintype "passive"))
      (node (ref "Q1") (pin "2") (pinfunction "S_2") (pintype "passive"))
      (node (ref "Q2") (pin "2") (pinfunction "S_2") (pintype "passive"))
      (node (ref "R1") (pin "P$2") (pinfunction "P$2_P$2") (pintype "passive"))
      (node (ref "R21") (pin "P$2") (pinfunction "P$2_P$2") (pintype "passive"))
      (node (ref "R22") (pin "P$2") (pinfunction "P$2_P$2") (pintype "passive"))
      (node (ref "U11") (pin "6") (pinfunction "VDD_1_6") (pintype "power_in"))
      (node (ref "U11") (pin "8") (pinfunction "VDD_2_8") (pintype "power_in"))
      (node (ref "U12") (pin "6") (pinfunction "VDD_1_6") (pintype "power_in"))
      (node (ref "U12") (pin "8") (pinfunction "VDD_2_8") (pintype "power_in"))
      (node (ref "U13") (pin "1") (pinfunction "VDD_1") (pintype "bidirectional"))
      (node (ref "U13") (pin "17") (pinfunction "VDD_17") (pintype "bidirectional"))
      (node (ref "U13") (pin "5") (pinfunction "VDDA_5") (pintype "bidirectional"))
      (node (ref "U15") (pin "4") (pinfunction "VCC_4") (pintype "bidirectional"))
      (node (ref "U2") (pin "P$6") (pinfunction "VBAT_P$6") (pintype "bidirectional"))
      (node (ref "U3") (pin "P$8") (pinfunction "EN_P$8") (pintype "bidirectional"))
      (node (ref "U3") (pin "P$9") (pinfunction "VCC_P$9") (pintype "bidirectional"))
    )
    (net (code "2") (name "BOOT0") (class "Default")
      (node (ref "BOOT0") (pin "TP") (pinfunction "TP_TP") (pintype "input"))
      (node (ref "R23") (pin "P$1") (pinfunction "P$1_P$1") (pintype "passive"))
      (node (ref "U13") (pin "31") (pinfunction "BOOT0_31") (pintype "bidirectional"))
    )
    (net (code "3") (name "CS1") (class "Default")
      (node (ref "U11") (pin "15") (pinfunction "NSEL_15") (pintype "input"))
      (node (ref "U13") (pin "10") (pinfunction "PA4_10") (pintype "bidirectional"))
    )
    (net (code "4") (name "CS2") (class "Default")
      (node (ref "U12") (pin "15") (pinfunction "NSEL_15") (pintype "input"))
      (node (ref "U13") (pin "6") (pinfunction "PA0_6") (pintype "bidirectional"))
    )
    (net (code "5") (name "GND") (class "Default")
      (node (ref "C1") (pin "P$2") (pinfunction "2_P$2") (pintype "passive"))
      (node (ref "C11") (pin "P$2") (pinfunction "2_P$2") (pintype "passive"))
      (node (ref "C13") (pin "P$2") (pinfunction "2_P$2") (pintype "passive"))
      (node (ref "C14") (pin "P$2") (pinfunction "2_P$2") (pintype "passive"))
      (node (ref "C15") (pin "P$2") (pinfunction "2_P$2") (pintype "passive"))
      (node (ref "C16") (pin "P$2") (pinfunction "2_P$2") (pintype "passive"))
      (node (ref "C17") (pin "P$2") (pinfunction "2_P$2") (pintype "passive"))
      (node (ref "C21") (pin "P$2") (pinfunction "2_P$2") (pintype "passive"))
      (node (ref "C23") (pin "P$2") (pinfunction "2_P$2") (pintype "passive"))
      (node (ref "C26") (pin "P$2") (pinfunction "2_P$2") (pintype "passive"))
      (node (ref "C28") (pin "P$2") (pinfunction "2_P$2") (pintype "passive"))
      (node (ref "C3") (pin "P$2") (pinfunction "2_P$2") (pintype "passive"))
      (node (ref "C30") (pin "P$2") (pinfunction "2_P$2") (pintype "passive"))
      (node (ref "C32") (pin "P$2") (pinfunction "2_P$2") (pintype "passive"))
      (node (ref "C34") (pin "P$2") (pinfunction "2_P$2") (pintype "passive"))
      (node (ref "C36") (pin "P$2") (pinfunction "2_P$2") (pintype "passive"))
      (node (ref "C37") (pin "P$2") (pinfunction "2_P$2") (pintype "passive"))
      (node (ref "C39") (pin "P$2") (pinfunction "2_P$2") (pintype "passive"))
      (node (ref "C4") (pin "P$2") (pinfunction "2_P$2") (pintype "passive"))
      (node (ref "C42") (pin "P$2") (pinfunction "2_P$2") (pintype "passive"))
      (node (ref "C43") (pin "P$2") (pinfunction "2_P$2") (pintype "passive"))
      (node (ref "C49") (pin "P$2") (pinfunction "2_P$2") (pintype "passive"))
      (node (ref "C5") (pin "P$2") (pinfunction "2_P$2") (pintype "passive"))
      (node (ref "C52") (pin "P$2") (pinfunction "2_P$2") (pintype "passive"))
      (node (ref "C53") (pin "P$2") (pinfunction "2_P$2") (pintype "passive"))
      (node (ref "C6") (pin "P$2") (pinfunction "2_P$2") (pintype "passive"))
      (node (ref "C7") (pin "P$2") (pinfunction "2_P$2") (pintype "passive"))
      (node (ref "C8") (pin "P$2") (pinfunction "2_P$2") (pintype "passive"))
      (node (ref "D1") (pin "A") (pinfunction "A_A") (pintype "passive"))
      (node (ref "D4") (pin "A") (pinfunction "A_A") (pintype "passive"))
      (node (ref "GND1") (pin "TP") (pinfunction "TP_TP") (pintype "input"))
      (node (ref "GND2") (pin "TP") (pinfunction "TP_TP") (pintype "input"))
      (node (ref "J$1") (pin "GND@0") (pinfunction "GND_GND@0") (pintype "bidirectional"))
      (node (ref "J$1") (pin "GND@1") (pinfunction "GND_GND@1") (pintype "bidirectional"))
      (node (ref "J$1") (pin "GND@2") (pinfunction "GND_GND@2") (pintype "bidirectional"))
      (node (ref "J$1") (pin "GND@3") (pinfunction "GND_GND@3") (pintype "bidirectional"))
      (node (ref "JLINK") (pin "1") (pinfunction "1_1") (pintype "passive"))
      (node (ref "JP1") (pin "8") (pinfunction "8_8") (pintype "bidirectional"))
      (node (ref "L14") (pin "P$1") (pinfunction "1_P$1") (pintype "passive"))
      (node (ref "R12") (pin "P$1") (pinfunction "P$1_P$1") (pintype "passive"))
      (node (ref "R18") (pin "P$1") (pinfunction "P$1_P$1") (pintype "passive"))
      (node (ref "R23") (pin "P$2") (pinfunction "P$2_P$2") (pintype "passive"))
      (node (ref "R24") (pin "P$1") (pinfunction "P$1_P$1") (pintype "passive"))
      (node (ref "R5") (pin "P$1") (pinfunction "P$1_P$1") (pintype "passive"))
      (node (ref "S1") (pin "P$2") (pinfunction "S2_P$2") (pintype "bidirectional"))
      (node (ref "SWDIO1") (pin "TP") (pinfunction "TP_TP") (pintype "input"))
      (node (ref "SWDIO2") (pin "TP") (pinfunction "TP_TP") (pintype "input"))
      (node (ref "SWDIO3") (pin "TP") (pinfunction "TP_TP") (pintype "input"))
      (node (ref "SWDIO4") (pin "TP") (pinfunction "TP_TP") (pintype "input"))
      (node (ref "SWDIO5") (pin "TP") (pinfunction "TP_TP") (pintype "input"))
      (node (ref "SWDIO6") (pin "TP") (pinfunction "TP_TP") (pintype "input"))
      (node (ref "U1") (pin "2") (pinfunction "GND_2") (pintype "bidirectional"))
      (node (ref "U11") (pin "18") (pinfunction "GNDX_18") (pintype "bidirectional"))
      (node (ref "U11") (pin "3") (pinfunction "RXN_3") (pintype "input"))
      (node (ref "U11") (pin "5") (pinfunction "NC_5") (pintype "bidirectional"))
      (node (ref "U11") (pin "EXP") (pinfunction "PAD_EXP") (pintype "bidirectional"))
      (node (ref "U12") (pin "18") (pinfunction "GNDX_18") (pintype "bidirectional"))
      (node (ref "U12") (pin "3") (pinfunction "RXN_3") (pintype "input"))
      (node (ref "U12") (pin "5") (pinfunction "NC_5") (pintype "bidirectional"))
      (node (ref "U12") (pin "EXP") (pinfunction "PAD_EXP") (pintype "bidirectional"))
      (node (ref "U13") (pin "16") (pinfunction "VSS_16") (pintype "bidirectional"))
      (node (ref "U13") (pin "32") (pinfunction "VSS_32") (pintype "bidirectional"))
      (node (ref "U13") (pin "EXP") (pinfunction "PAD_EXP") (pintype "bidirectional"))
      (node (ref "U14") (pin "1") (pinfunction "S_1") (pintype "bidirectional"))
      (node (ref "U14") (pin "4") (pinfunction "S_4") (pintype "bidirectional"))
      (node (ref "U15") (pin "2") (pinfunction "GND_2") (pintype "bidirectional"))
      (node (ref "U15") (pin "5") (pinfunction "WP_5") (pintype "bidirectional"))
      (node (ref "U17") (pin "1") (pinfunction "S_1") (pintype "bidirectional"))
      (node (ref "U17") (pin "4") (pinfunction "S_4") (pintype "bidirectional"))
      (node (ref "U2") (pin "P$1") (pinfunction "GND_P$1") (pintype "bidirectional"))
      (node (ref "U2") (pin "P$10") (pinfunction "GND_P$10") (pintype "bidirectional"))
      (node (ref "U2") (pin "P$12") (pinfunction "GND_P$12") (pintype "bidirectional"))
      (node (ref "U3") (pin "P$1") (pinfunction "GND_P$1") (pintype "bidirectional"))
      (node (ref "U3") (pin "P$10") (pinfunction "GND_P$10") (pintype "bidirectional"))
      (node (ref "U3") (pin "P$12") (pinfunction "GND_P$12") (pintype "bidirectional"))
      (node (ref "U3") (pin "P$13") (pinfunction "GND_P$13") (pintype "bidirectional"))
      (node (ref "U3") (pin "P$3") (pinfunction "GND_P$3") (pintype "bidirectional"))
      (node (ref "U3") (pin "P$4") (pinfunction "GND_P$4") (pintype "bidirectional"))
      (node (ref "U3") (pin "P$6") (pinfunction "GND_P$6") (pintype "bidirectional"))
      (node (ref "U5") (pin "2") (pinfunction "GND_2") (pintype "bidirectional"))
      (node (ref "U5") (pin "4") (pinfunction "GND_4") (pintype "bidirectional"))
      (node (ref "U5") (pin "5") (pinfunction "GND_5") (pintype "bidirectional"))
      (node (ref "U6") (pin "3") (pinfunction "P$3_3") (pintype "bidirectional"))
      (node (ref "U7") (pin "2") (pinfunction "S_2") (pintype "passive"))
      (node (ref "U7") (pin "2@1") (pinfunction "PAD_2@1") (pintype "bidirectional"))
      (node (ref "U9") (pin "P$3") (pinfunction "GND_P$3") (pintype "bidirectional"))
      (node (ref "X1") (pin "2") (pinfunction "G2_2") (pintype "power_in"))
      (node (ref "X1") (pin "4") (pinfunction "G1_4") (pintype "power_in"))
      (node (ref "X2") (pin "2") (pinfunction "G2_2") (pintype "power_in"))
      (node (ref "X2") (pin "4") (pinfunction "G1_4") (pintype "power_in"))
      (node (ref "Z2") (pin "P$1") (pinfunction "P$1_P$1") (pintype "passive"))
      (node (ref "Z3") (pin "P$1") (pinfunction "P$1_P$1") (pintype "passive"))
    )
    (net (code "6") (name "GPS_1PPS") (class "Default")
      (node (ref "U13") (pin "8") (pinfunction "PA2_8") (pintype "bidirectional"))
      (node (ref "U2") (pin "P$4") (pinfunction "1PPS_P$4") (pintype "bidirectional"))
    )
    (net (code "7") (name "GPS_EN") (class "Default")
      (node (ref "Q2") (pin "1") (pinfunction "G_1") (pintype "passive"))
      (node (ref "R1") (pin "P$1") (pinfunction "P$1_P$1") (pintype "passive"))
      (node (ref "U13") (pin "2") (pinfunction "OSC_IN/PC14_2") (pintype "bidirectional"))
    )
    (net (code "8") (name "GPS_STATUS") (class "Default")
      (node (ref "U13") (pin "21") (pinfunction "PA11_21") (pintype "bidirectional"))
      (node (ref "U14") (pin "5") (pinfunction "G_5") (pintype "bidirectional"))
    )
    (net (code "9") (name "GPS_UART_TX") (class "Default")
      (node (ref "U13") (pin "9") (pinfunction "PA3_9") (pintype "bidirectional"))
      (node (ref "U2") (pin "P$2") (pinfunction "TX_P$2") (pintype "bidirectional"))
    )
    (net (code "10") (name "HOST_GPS_STATUS") (class "Default")
      (node (ref "JP1") (pin "4") (pinfunction "4_4") (pintype "bidirectional"))
      (node (ref "R14") (pin "P$2") (pinfunction "P$2_P$2") (pintype "passive"))
      (node (ref "U9") (pin "P$2") (pinfunction "C2_P$2") (pintype "bidirectional"))
    )
    (net (code "11") (name "HOST_RX_STATUS") (class "Default")
      (node (ref "JP1") (pin "6") (pinfunction "6_6") (pintype "bidirectional"))
      (node (ref "R15") (pin "P$2") (pinfunction "P$2_P$2") (pintype "passive"))
      (node (ref "U9") (pin "P$7") (pinfunction "C6_P$7") (pintype "bidirectional"))
    )
    (net (code "12") (name "HOST_TX_OFF") (class "Default")
      (node (ref "JP1") (pin "2") (pinfunction "2_2") (pintype "bidirectional"))
      (node (ref "R18") (pin "P$2") (pinfunction "P$2_P$2") (pintype "passive"))
      (node (ref "U17") (pin "2") (pinfunction "G_2") (pintype "bidirectional"))
      (node (ref "U9") (pin "P$1") (pinfunction "C1_P$1") (pintype "bidirectional"))
    )
    (net (code "13") (name "HOST_TX_STATUS") (class "Default")
      (node (ref "JP1") (pin "7") (pinfunction "7_7") (pintype "bidirectional"))
      (node (ref "R17") (pin "P$2") (pinfunction "P$2_P$2") (pintype "passive"))
      (node (ref "U9") (pin "P$6") (pinfunction "C5_P$6") (pintype "bidirectional"))
    )
    (net (code "14") (name "HOST_UART_RX") (class "Default")
      (node (ref "JP1") (pin "5") (pinfunction "5_5") (pintype "bidirectional"))
      (node (ref "R13") (pin "P$2") (pinfunction "P$2_P$2") (pintype "passive"))
      (node (ref "U9") (pin "P$8") (pinfunction "C7_P$8") (pintype "bidirectional"))
    )
    (net (code "15") (name "HOST_UART_TX") (class "Default")
      (node (ref "JP1") (pin "3") (pinfunction "3_3") (pintype "bidirectional"))
      (node (ref "R2") (pin "P$2") (pinfunction "P$2_P$2") (pintype "passive"))
      (node (ref "U9") (pin "P$9") (pinfunction "C8_P$9") (pintype "bidirectional"))
    )
    (net (code "16") (name "I2C_SCL") (class "Default")
      (node (ref "U13") (pin "29") (pinfunction "PB6_29") (pintype "bidirectional"))
      (node (ref "U15") (pin "1") (pinfunction "SCL_1") (pintype "bidirectional"))
    )
    (net (code "17") (name "I2C_SDA") (class "Default")
      (node (ref "U13") (pin "30") (pinfunction "PB7_30") (pintype "bidirectional"))
      (node (ref "U15") (pin "3") (pinfunction "SDA_3") (pintype "bidirectional"))
    )
    (net (code "18") (name "MCU_TX_OFF") (class "Default")
      (node (ref "U13") (pin "22") (pinfunction "PA12_22") (pintype "bidirectional"))
      (node (ref "U17") (pin "6") (pinfunction "D_6") (pintype "bidirectional"))
    )
    (net (code "19") (name "MCU_UART_RX") (class "Default")
      (node (ref "R2") (pin "P$1") (pinfunction "P$1_P$1") (pintype "passive"))
      (node (ref "RX") (pin "TP") (pinfunction "TP_TP") (pintype "input"))
      (node (ref "U13") (pin "20") (pinfunction "PA10_20") (pintype "bidirectional"))
      (node (ref "U6") (pin "1") (pinfunction "P$1_1") (pintype "bidirectional"))
    )
    (net (code "20") (name "MCU_UART_TX") (class "Default")
      (node (ref "R13") (pin "P$1") (pinfunction "P$1_P$1") (pintype "passive"))
      (node (ref "TX") (pin "TP") (pinfunction "TP_TP") (pintype "input"))
      (node (ref "U13") (pin "19") (pinfunction "PA9_19") (pintype "bidirectional"))
      (node (ref "U6") (pin "2") (pinfunction "P$2_2") (pintype "bidirectional"))
    )
    (net (code "21") (name "MISO") (class "Default")
      (node (ref "U11") (pin "13") (pinfunction "SDO_13") (pintype "output"))
      (node (ref "U12") (pin "13") (pinfunction "SDO_13") (pintype "output"))
      (node (ref "U13") (pin "12") (pinfunction "PA6_12") (pintype "bidirectional"))
    )
    (net (code "22") (name "MOSI") (class "Default")
      (node (ref "U11") (pin "14") (pinfunction "SDI_14") (pintype "input"))
      (node (ref "U12") (pin "14") (pinfunction "SDI_14") (pintype "input"))
      (node (ref "U13") (pin "13") (pinfunction "PA7_13") (pintype "bidirectional"))
    )
    (net (code "23") (name "NRST") (class "Default")
      (node (ref "JLINK") (pin "2") (pinfunction "2_2") (pintype "passive"))
      (node (ref "NRST") (pin "TP") (pinfunction "TP_TP") (pintype "input"))
      (node (ref "S1") (pin "P$1") (pinfunction "S1_P$1") (pintype "bidirectional"))
      (node (ref "U13") (pin "4") (pinfunction "NRST_4") (pintype "bidirectional"))
    )
    (net (code "24") (name "Net-(C1-1)") (class "Default")
      (node (ref "C1") (pin "P$1") (pinfunction "1_P$1") (pintype "passive"))
      (node (ref "C43") (pin "P$1") (pinfunction "1_P$1") (pintype "passive"))
      (node (ref "L2") (pin "P$2") (pinfunction "2_P$2") (pintype "passive"))
      (node (ref "U1") (pin "4") (pinfunction "EN_4") (pintype "bidirectional"))
      (node (ref "U1") (pin "5") (pinfunction "IN_5") (pintype "bidirectional"))
    )
    (net (code "25") (name "Net-(C2-1)") (class "Default")
      (node (ref "C2") (pin "P$1") (pinfunction "1_P$1") (pintype "passive"))
      (node (ref "U1") (pin "1") (pinfunction "BS_1") (pintype "bidirectional"))
    )
    (net (code "26") (name "Net-(C2-2)") (class "Default")
      (node (ref "C2") (pin "P$2") (pinfunction "2_P$2") (pintype "passive"))
      (node (ref "D4") (pin "C") (pinfunction "C_C") (pintype "passive"))
      (node (ref "L12") (pin "P$1") (pinfunction "1_P$1") (pintype "passive"))
      (node (ref "U1") (pin "6") (pinfunction "SW_6") (pintype "bidirectional"))
    )
    (net (code "27") (name "Net-(C3-1)") (class "Default")
      (node (ref "C3") (pin "P$1") (pinfunction "1_P$1") (pintype "passive"))
      (node (ref "C5") (pin "P$1") (pinfunction "1_P$1") (pintype "passive"))
      (node (ref "Q2") (pin "3") (pinfunction "D_3") (pintype "passive"))
      (node (ref "U2") (pin "P$8") (pinfunction "VCC_P$8") (pintype "bidirectional"))
    )
    (net (code "28") (name "Net-(C9-1)") (class "Default")
      (node (ref "C9") (pin "P$1") (pinfunction "1_P$1") (pintype "passive"))
      (node (ref "L8") (pin "P$2") (pinfunction "2_P$2") (pintype "passive"))
    )
    (net (code "29") (name "Net-(C10-1)") (class "Default")
      (node (ref "C10") (pin "P$1") (pinfunction "1_P$1") (pintype "passive"))
      (node (ref "C8") (pin "P$1") (pinfunction "1_P$1") (pintype "passive"))
      (node (ref "C9") (pin "P$2") (pinfunction "2_P$2") (pintype "passive"))
      (node (ref "L14") (pin "P$2") (pinfunction "2_P$2") (pintype "passive"))
    )
    (net (code "30") (name "Net-(C10-2)") (class "Default")
      (node (ref "C10") (pin "P$2") (pinfunction "2_P$2") (pintype "passive"))
      (node (ref "L13") (pin "P$1") (pinfunction "1_P$1") (pintype "passive"))
    )
    (net (code "31") (name "Net-(C12-1)") (class "Default")
      (node (ref "C12") (pin "P$1") (pinfunction "1_P$1") (pintype "passive"))
      (node (ref "L13") (pin "P$2") (pinfunction "2_P$2") (pintype "passive"))
    )
    (net (code "32") (name "Net-(C12-2)") (class "Default")
      (node (ref "C12") (pin "P$2") (pinfunction "2_P$2") (pintype "passive"))
      (node (ref "U5") (pin "6") (pinfunction "IN_6") (pintype "bidirectional"))
    )
    (net (code "33") (name "Net-(C13-1)") (class "Default")
      (node (ref "C13") (pin "P$1") (pinfunction "1_P$1") (pintype "passive"))
      (node (ref "R10") (pin "P$2") (pinfunction "P$2_P$2") (pintype "passive"))
      (node (ref "U5") (pin "1") (pinfunction "VCC_1") (pintype "bidirectional"))
    )
    (net (code "34") (name "Net-(C18-1)") (class "Default")
      (node (ref "C18") (pin "P$1") (pinfunction "1_P$1") (pintype "passive"))
      (node (ref "U5") (pin "3") (pinfunction "OUT_3") (pintype "bidirectional"))
    )
    (net (code "35") (name "Net-(C21-1)") (class "Default")
      (node (ref "C21") (pin "P$1") (pinfunction "1_P$1") (pintype "passive"))
      (node (ref "L5") (pin "P$1") (pinfunction "1_P$1") (pintype "passive"))
      (node (ref "R22") (pin "P$1") (pinfunction "P$1_P$1") (pintype "passive"))
    )
    (net (code "36") (name "Net-(C22-1)") (class "Default")
      (node (ref "C22") (pin "P$1") (pinfunction "1_P$1") (pintype "passive"))
      (node (ref "L5") (pin "P$2") (pinfunction "2_P$2") (pintype "passive"))
      (node (ref "U11") (pin "4") (pinfunction "TX_4") (pintype "output"))
    )
    (net (code "37") (name "Net-(C22-2)") (class "Default")
      (node (ref "C22") (pin "P$2") (pinfunction "2_P$2") (pintype "passive"))
      (node (ref "L1") (pin "P$1") (pinfunction "1_P$1") (pintype "passive"))
    )
    (net (code "38") (name "Net-(C23-1)") (class "Default")
      (node (ref "C23") (pin "P$1") (pinfunction "1_P$1") (pintype "passive"))
      (node (ref "L1") (pin "P$2") (pinfunction "2_P$2") (pintype "passive"))
      (node (ref "L6") (pin "P$1") (pinfunction "1_P$1") (pintype "passive"))
    )
    (net (code "39") (name "Net-(C29-2)") (class "Default")
      (node (ref "C29") (pin "P$2") (pinfunction "2_P$2") (pintype "passive"))
      (node (ref "C30") (pin "P$1") (pinfunction "1_P$1") (pintype "passive"))
      (node (ref "L3") (pin "P$1") (pinfunction "1_P$1") (pintype "passive"))
    )
    (net (code "40") (name "Net-(C36-1)") (class "Default")
      (node (ref "C36") (pin "P$1") (pinfunction "1_P$1") (pintype "passive"))
      (node (ref "L10") (pin "P$1") (pinfunction "1_P$1") (pintype "passive"))
      (node (ref "L9") (pin "P$2") (pinfunction "2_P$2") (pintype "passive"))
    )
    (net (code "41") (name "Net-(C37-1)") (class "Default")
      (node (ref "C37") (pin "P$1") (pinfunction "1_P$1") (pintype "passive"))
      (node (ref "C39") (pin "P$1") (pinfunction "1_P$1") (pintype "passive"))
      (node (ref "L4") (pin "P$2") (pinfunction "2_P$2") (pintype "passive"))
      (node (ref "L9") (pin "P$1") (pinfunction "1_P$1") (pintype "passive"))
      (node (ref "U7") (pin "3") (pinfunction "D_3") (pintype "passive"))
    )
    (net (code "42") (name "Net-(C42-1)") (class "Default")
      (node (ref "C42") (pin "P$1") (pinfunction "1_P$1") (pintype "passive"))
      (node (ref "C52") (pin "P$1") (pinfunction "1_P$1") (pintype "passive"))
      (node (ref "L10") (pin "P$2") (pinfunction "2_P$2") (pintype "passive"))
      (node (ref "L23") (pin "P$1") (pinfunction "1_P$1") (pintype "passive"))
    )
    (net (code "43") (name "Net-(C44-1)") (class "Default")
      (node (ref "C44") (pin "P$1") (pinfunction "1_P$1") (pintype "passive"))
      (node (ref "C53") (pin "P$1") (pinfunction "1_P$1") (pintype "passive"))
      (node (ref "L23") (pin "P$2") (pinfunction "2_P$2") (pintype "passive"))
    )
    (net (code "44") (name "Net-(J$1-SIGNAL)") (class "Default")
      (node (ref "J$1") (pin "SIG") (pinfunction "SIGNAL_SIG") (pintype "bidirectional"))
      (node (ref "RF") (pin "TP") (pinfunction "TP_TP") (pintype "input"))
      (node (ref "U3") (pin "P$2") (pinfunction "RF1_P$2") (pintype "bidirectional"))
    )
    (net (code "45") (name "Net-(L17-1)") (class "Default")
      (node (ref "L17") (pin "P$1") (pinfunction "1_P$1") (pintype "passive"))
      (node (ref "L3") (pin "P$2") (pinfunction "2_P$2") (pintype "passive"))
      (node (ref "U7") (pin "1") (pinfunction "G_1") (pintype "passive"))
    )
    (net (code "46") (name "Net-(Q3-B)") (class "Default")
      (node (ref "D1") (pin "C") (pinfunction "C_C") (pintype "passive"))
      (node (ref "Q3") (pin "1") (pinfunction "B_1") (pintype "passive"))
      (node (ref "R3") (pin "P$1") (pinfunction "P$1_P$1") (pintype "passive"))
    )
    (net (code "47") (name "Net-(U1-FB)") (class "Default")
      (node (ref "R21") (pin "P$1") (pinfunction "P$1_P$1") (pintype "passive"))
      (node (ref "R24") (pin "P$2") (pinfunction "P$2_P$2") (pintype "passive"))
      (node (ref "U1") (pin "3") (pinfunction "FB_3") (pintype "bidirectional"))
    )
    (net (code "48") (name "Net-(U2-RFIN)") (class "Default")
      (node (ref "U2") (pin "P$11") (pinfunction "RFIN_P$11") (pintype "bidirectional"))
      (node (ref "Z1") (pin "P$2") (pinfunction "P$2_P$2") (pintype "passive"))
      (node (ref "Z3") (pin "P$2") (pinfunction "P$2_P$2") (pintype "passive"))
    )
    (net (code "49") (name "Net-(U10-RF)") (class "Default")
      (node (ref "U10") (pin "P$1") (pinfunction "RF_P$1") (pintype "bidirectional"))
      (node (ref "Z1") (pin "P$1") (pinfunction "P$1_P$1") (pintype "passive"))
      (node (ref "Z2") (pin "P$2") (pinfunction "P$2_P$2") (pintype "passive"))
    )
    (net (code "50") (name "Net-(U11-XIN)") (class "Default")
      (node (ref "U11") (pin "17") (pinfunction "XIN_17") (pintype "input"))
      (node (ref "X1") (pin "3") (pinfunction "X2_3") (pintype "bidirectional"))
    )
    (net (code "51") (name "Net-(U11-XOUT)") (class "Default")
      (node (ref "U11") (pin "16") (pinfunction "XOUT_16") (pintype "bidirectional"))
      (node (ref "X1") (pin "1") (pinfunction "X1_1") (pintype "bidirectional"))
    )
    (net (code "52") (name "Net-(U12-XIN)") (class "Default")
      (node (ref "U12") (pin "17") (pinfunction "XIN_17") (pintype "input"))
      (node (ref "X2") (pin "3") (pinfunction "X2_3") (pintype "bidirectional"))
    )
    (net (code "53") (name "Net-(U12-XOUT)") (class "Default")
      (node (ref "U12") (pin "16") (pinfunction "XOUT_16") (pintype "bidirectional"))
      (node (ref "X2") (pin "1") (pinfunction "X1_1") (pintype "bidirectional"))
    )
    (net (code "54") (name "Net-(U14A-D)") (class "Default")
      (node (ref "R14") (pin "P$1") (pinfunction "P$1_P$1") (pintype "passive"))
      (node (ref "U14") (pin "3") (pinfunction "D_3") (pintype "bidirectional"))
    )
    (net (code "55") (name "Net-(U14B-D)") (class "Default")
      (node (ref "R15") (pin "P$1") (pinfunction "P$1_P$1") (pintype "passive"))
      (node (ref "U14") (pin "6") (pinfunction "D_6") (pintype "bidirectional"))
    )
    (net (code "56") (name "Net-(U17A-D)") (class "Default")
      (node (ref "R17") (pin "P$1") (pinfunction "P$1_P$1") (pintype "passive"))
      (node (ref "U17") (pin "3") (pinfunction "D_3") (pintype "bidirectional"))
    )
    (net (code "57") (name "PA_GATE_BIAS") (class "Default")
      (node (ref "C11") (pin "P$1") (pinfunction "1_P$1") (pintype "passive"))
      (node (ref "L17") (pin "P$2") (pinfunction "2_P$2") (pintype "passive"))
      (node (ref "R11") (pin "P$1") (pinfunction "P$1_P$1") (pintype "passive"))
      (node (ref "R12") (pin "P$2") (pinfunction "P$2_P$2") (pintype "passive"))
    )
    (net (code "58") (name "PA_IN") (class "Default")
      (node (ref "C29") (pin "P$1") (pinfunction "1_P$1") (pintype "passive"))
      (node (ref "L6") (pin "P$2") (pinfunction "2_P$2") (pintype "passive"))
    )
    (net (code "59") (name "PA_OUT") (class "Default")
      (node (ref "C44") (pin "P$2") (pinfunction "2_P$2") (pintype "passive"))
      (node (ref "U3") (pin "P$5") (pinfunction "RF3_P$5") (pintype "bidirectional"))
    )
    (net (code "60") (name "RFSW_CTRL") (class "Default")
      (node (ref "Q1") (pin "1") (pinfunction "G_1") (pintype "passive"))
      (node (ref "U11") (pin "20") (pinfunction "GPIO3_20") (pintype "bidirectional"))
    )
    (net (code "61") (name "RF_IN") (class "Default")
      (node (ref "L8") (pin "P$1") (pinfunction "1_P$1") (pintype "passive"))
      (node (ref "U3") (pin "P$11") (pinfunction "RF2_P$11") (pintype "bidirectional"))
    )
    (net (code "62") (name "RX_EN") (class "Default")
      (node (ref "R4") (pin "P$2") (pinfunction "P$2_P$2") (pintype "passive"))
      (node (ref "R5") (pin "P$2") (pinfunction "P$2_P$2") (pintype "passive"))
      (node (ref "U3") (pin "P$7") (pinfunction "CTRL_P$7") (pintype "bidirectional"))
    )
    (net (code "63") (name "RX_IC_CLK") (class "Default")
      (node (ref "U12") (pin "20") (pinfunction "GPIO3_20") (pintype "bidirectional"))
      (node (ref "U13") (pin "26") (pinfunction "PB3_26") (pintype "bidirectional"))
    )
    (net (code "64") (name "RX_IC_DATA") (class "Default")
      (node (ref "U12") (pin "10") (pinfunction "GPIO1_10") (pintype "bidirectional"))
      (node (ref "U13") (pin "27") (pinfunction "PB4_27") (pintype "bidirectional"))
    )
    (net (code "65") (name "RX_IN") (class "Default")
      (node (ref "C18") (pin "P$2") (pinfunction "2_P$2") (pintype "passive"))
      (node (ref "U11") (pin "2") (pinfunction "RXP_2") (pintype "input"))
      (node (ref "U12") (pin "2") (pinfunction "RXP_2") (pintype "input"))
    )
    (net (code "66") (name "RX_STATUS") (class "Default")
      (node (ref "U13") (pin "7") (pinfunction "PA1_7") (pintype "bidirectional"))
      (node (ref "U14") (pin "2") (pinfunction "G_2") (pintype "bidirectional"))
    )
    (net (code "67") (name "SCK") (class "Default")
      (node (ref "U11") (pin "12") (pinfunction "SCLK_12") (pintype "input"))
      (node (ref "U12") (pin "12") (pinfunction "SCLK_12") (pintype "input"))
      (node (ref "U13") (pin "11") (pinfunction "PA5_11") (pintype "bidirectional"))
    )
    (net (code "68") (name "SDN1") (class "Default")
      (node (ref "U11") (pin "1") (pinfunction "SDN_1") (pintype "input"))
      (node (ref "U13") (pin "14") (pinfunction "PB0_14") (pintype "bidirectional"))
    )
    (net (code "69") (name "SDN2") (class "Default")
      (node (ref "U12") (pin "1") (pinfunction "SDN_1") (pintype "input"))
      (node (ref "U13") (pin "25") (pinfunction "PA15_25") (pintype "bidirectional"))
    )
    (net (code "70") (name "SWCLK") (class "Default")
      (node (ref "JLINK") (pin "3") (pinfunction "3_3") (pintype "passive"))
      (node (ref "SWCLK") (pin "TP") (pinfunction "TP_TP") (pintype "input"))
      (node (ref "U13") (pin "24") (pinfunction "PA14_24") (pintype "bidirectional"))
    )
    (net (code "71") (name "SWDIO") (class "Default")
      (node (ref "JLINK") (pin "4") (pinfunction "4_4") (pintype "passive"))
      (node (ref "SWDIO") (pin "TP") (pinfunction "TP_TP") (pintype "input"))
      (node (ref "U13") (pin "23") (pinfunction "PA13_23") (pintype "bidirectional"))
    )
    (net (code "72") (name "TRX_IC_CLOCK") (class "Default")
      (node (ref "U11") (pin "19") (pinfunction "GPIO2_19") (pintype "bidirectional"))
      (node (ref "U13") (pin "3") (pinfunction "OSC_OUT/PC15_3") (pintype "bidirectional"))
    )
    (net (code "73") (name "TRX_IC_DATA") (class "Default")
      (node (ref "U11") (pin "10") (pinfunction "GPIO1_10") (pintype "bidirectional"))
      (node (ref "U13") (pin "15") (pinfunction "PB1_15") (pintype "bidirectional"))
    )
    (net (code "74") (name "TX_STATUS") (class "Default")
      (node (ref "U13") (pin "28") (pinfunction "PB5_28") (pintype "bidirectional"))
      (node (ref "U17") (pin "5") (pinfunction "G_5") (pintype "bidirectional"))
    )
    (net (code "75") (name "V_IN") (class "Default")
      (node (ref "C4") (pin "P$1") (pinfunction "1_P$1") (pintype "passive"))
      (node (ref "JP1") (pin "1") (pinfunction "1_1") (pintype "bidirectional"))
      (node (ref "L2") (pin "P$1") (pinfunction "1_P$1") (pintype "passive"))
      (node (ref "Q3") (pin "3") (pinfunction "C_3") (pintype "passive"))
      (node (ref "R3") (pin "P$2") (pinfunction "P$2_P$2") (pintype "passive"))
      (node (ref "V_IN") (pin "TP") (pinfunction "TP_TP") (pintype "input"))
    )
    (net (code "76") (name "V_LNA") (class "Default")
      (node (ref "Q1") (pin "3") (pinfunction "D_3") (pintype "passive"))
      (node (ref "R10") (pin "P$1") (pinfunction "P$1_P$1") (pintype "passive"))
      (node (ref "R4") (pin "P$1") (pinfunction "P$1_P$1") (pintype "passive"))
      (node (ref "V_LNA") (pin "TP") (pinfunction "TP_TP") (pintype "input"))
    )
    (net (code "77") (name "V_PA") (class "Default")
      (node (ref "C49") (pin "P$1") (pinfunction "1_P$1") (pintype "passive"))
      (node (ref "C7") (pin "P$1") (pinfunction "1_P$1") (pintype "passive"))
      (node (ref "L4") (pin "P$1") (pinfunction "1_P$1") (pintype "passive"))
      (node (ref "Q3") (pin "2") (pinfunction "E_2") (pintype "passive"))
      (node (ref "V_PA") (pin "TP") (pinfunction "TP_TP") (pintype "input"))
    )
    (net (code "78") (name "V_PA_BIAS") (class "Default")
      (node (ref "R11") (pin "P$2") (pinfunction "P$2_P$2") (pintype "passive"))
      (node (ref "U13") (pin "18") (pinfunction "PA8_18") (pintype "bidirectional"))
    )
    (net (code "79") (name "unconnected-(S1-S1-PadP$4)") (class "Default")
      (node (ref "S1") (pin "P$4") (pinfunction "S1_P$4") (pintype "bidirectional"))
    )
    (net (code "80") (name "unconnected-(S1-S2-PadP$3)") (class "Default")
      (node (ref "S1") (pin "P$3") (pinfunction "S2_P$3") (pintype "bidirectional"))
    )
    (net (code "81") (name "unconnected-(U2-RX-PadP$3)") (class "Default")
      (node (ref "U2") (pin "P$3") (pinfunction "RX_P$3") (pintype "bidirectional"))
    )
    (net (code "82") (name "unconnected-(U2-VIO-PadP$7)") (class "Default")
      (node (ref "U2") (pin "P$7") (pinfunction "VIO_P$7") (pintype "bidirectional"))
    )
    (net (code "83") (name "unconnected-(U9-C3-PadP$4)") (class "Default")
      (node (ref "U9") (pin "P$4") (pinfunction "C3_P$4") (pintype "bidirectional"))
    )
    (net (code "84") (name "unconnected-(U9-C4-PadP$5)") (class "Default")
      (node (ref "U9") (pin "P$5") (pinfunction "C4_P$5") (pintype "bidirectional"))
    )
    (net (code "85") (name "unconnected-(U10-PAD-PadP$2)") (class "Default")
      (node (ref "U10") (pin "P$2") (pinfunction "PAD_P$2") (pintype "no_connect"))
    )
    (net (code "86") (name "unconnected-(U11-GPIO0-Pad9)") (class "Default")
      (node (ref "U11") (pin "9") (pinfunction "GPIO0_9") (pintype "bidirectional"))
    )
    (net (code "87") (name "unconnected-(U11-NIRQ-Pad11)") (class "Default")
      (node (ref "U11") (pin "11") (pinfunction "NIRQ_11") (pintype "bidirectional"))
    )
    (net (code "88") (name "unconnected-(U11-TXRAMP-Pad7)") (class "Default")
      (node (ref "U11") (pin "7") (pinfunction "TXRAMP_7") (pintype "bidirectional"))
    )
    (net (code "89") (name "unconnected-(U12-GPIO0-Pad9)") (class "Default")
      (node (ref "U12") (pin "9") (pinfunction "GPIO0_9") (pintype "bidirectional"))
    )
    (net (code "90") (name "unconnected-(U12-GPIO2-Pad19)") (class "Default")
      (node (ref "U12") (pin "19") (pinfunction "GPIO2_19") (pintype "bidirectional"))
    )
    (net (code "91") (name "unconnected-(U12-NIRQ-Pad11)") (class "Default")
      (node (ref "U12") (pin "11") (pinfunction "NIRQ_11") (pintype "bidirectional"))
    )
    (net (code "92") (name "unconnected-(U12-TX-Pad4)") (class "Default")
      (node (ref "U12") (pin "4") (pinfunction "TX_4") (pintype "output"))
    )
    (net (code "93") (name "unconnected-(U12-TXRAMP-Pad7)") (class "Default")
      (node (ref "U12") (pin "7") (pinfunction "TXRAMP_7") (pintype "bidirectional"))
    )
  )
)
